# counterMeter.net
KiCad netlist of a schematic drawn in EAGLE
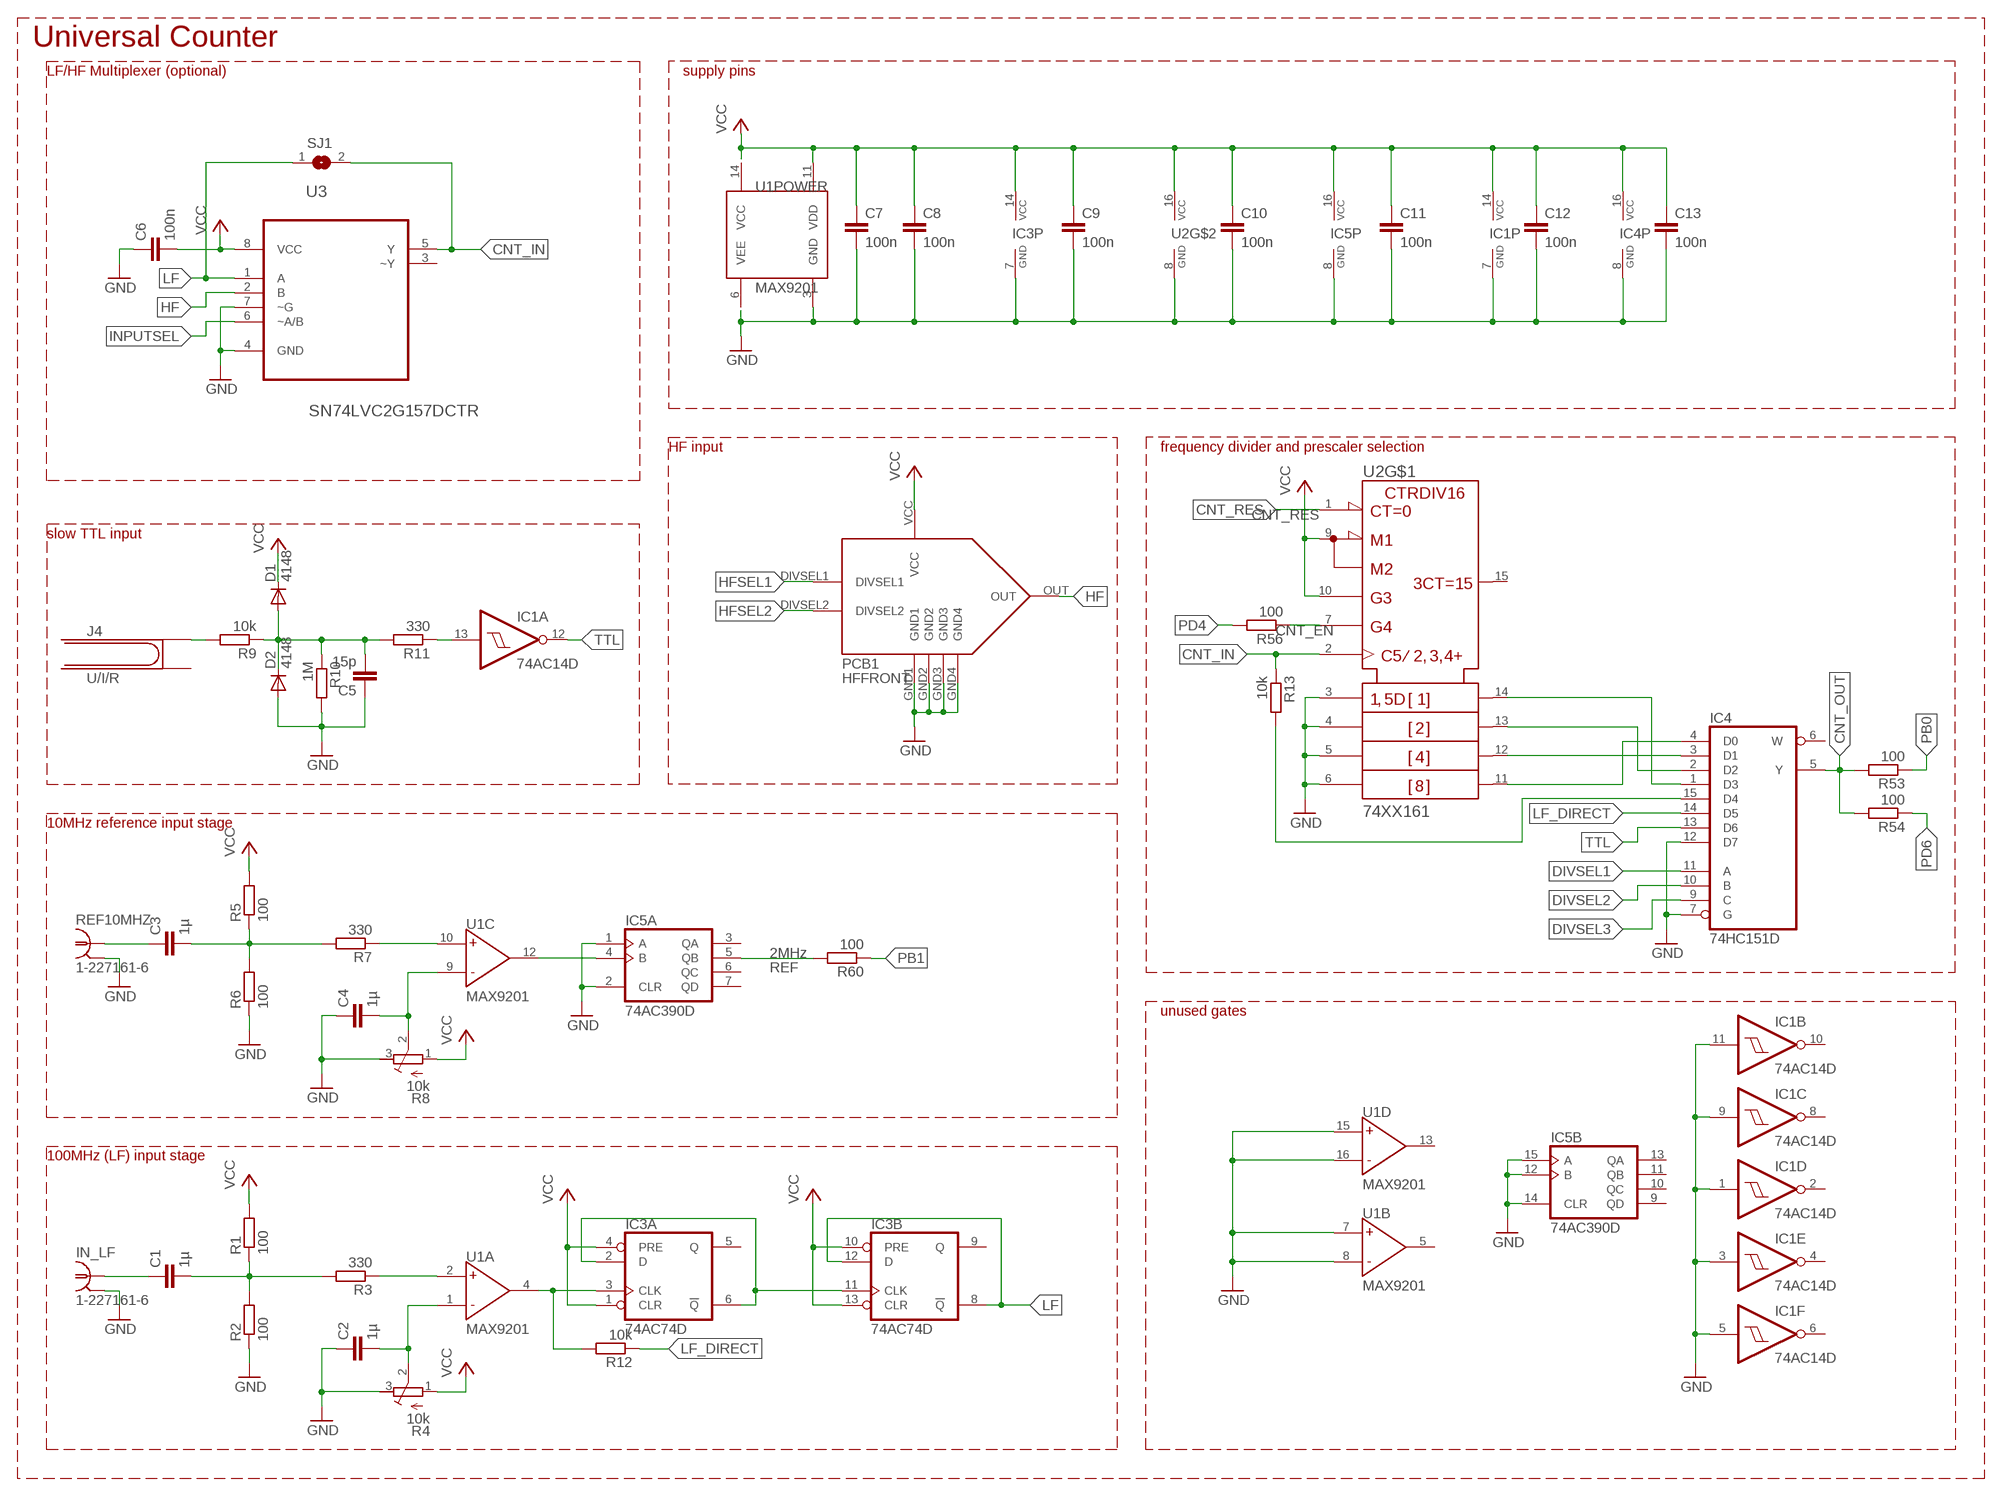
[diagram p0: schematic, sheet 1, part 1 of 2]
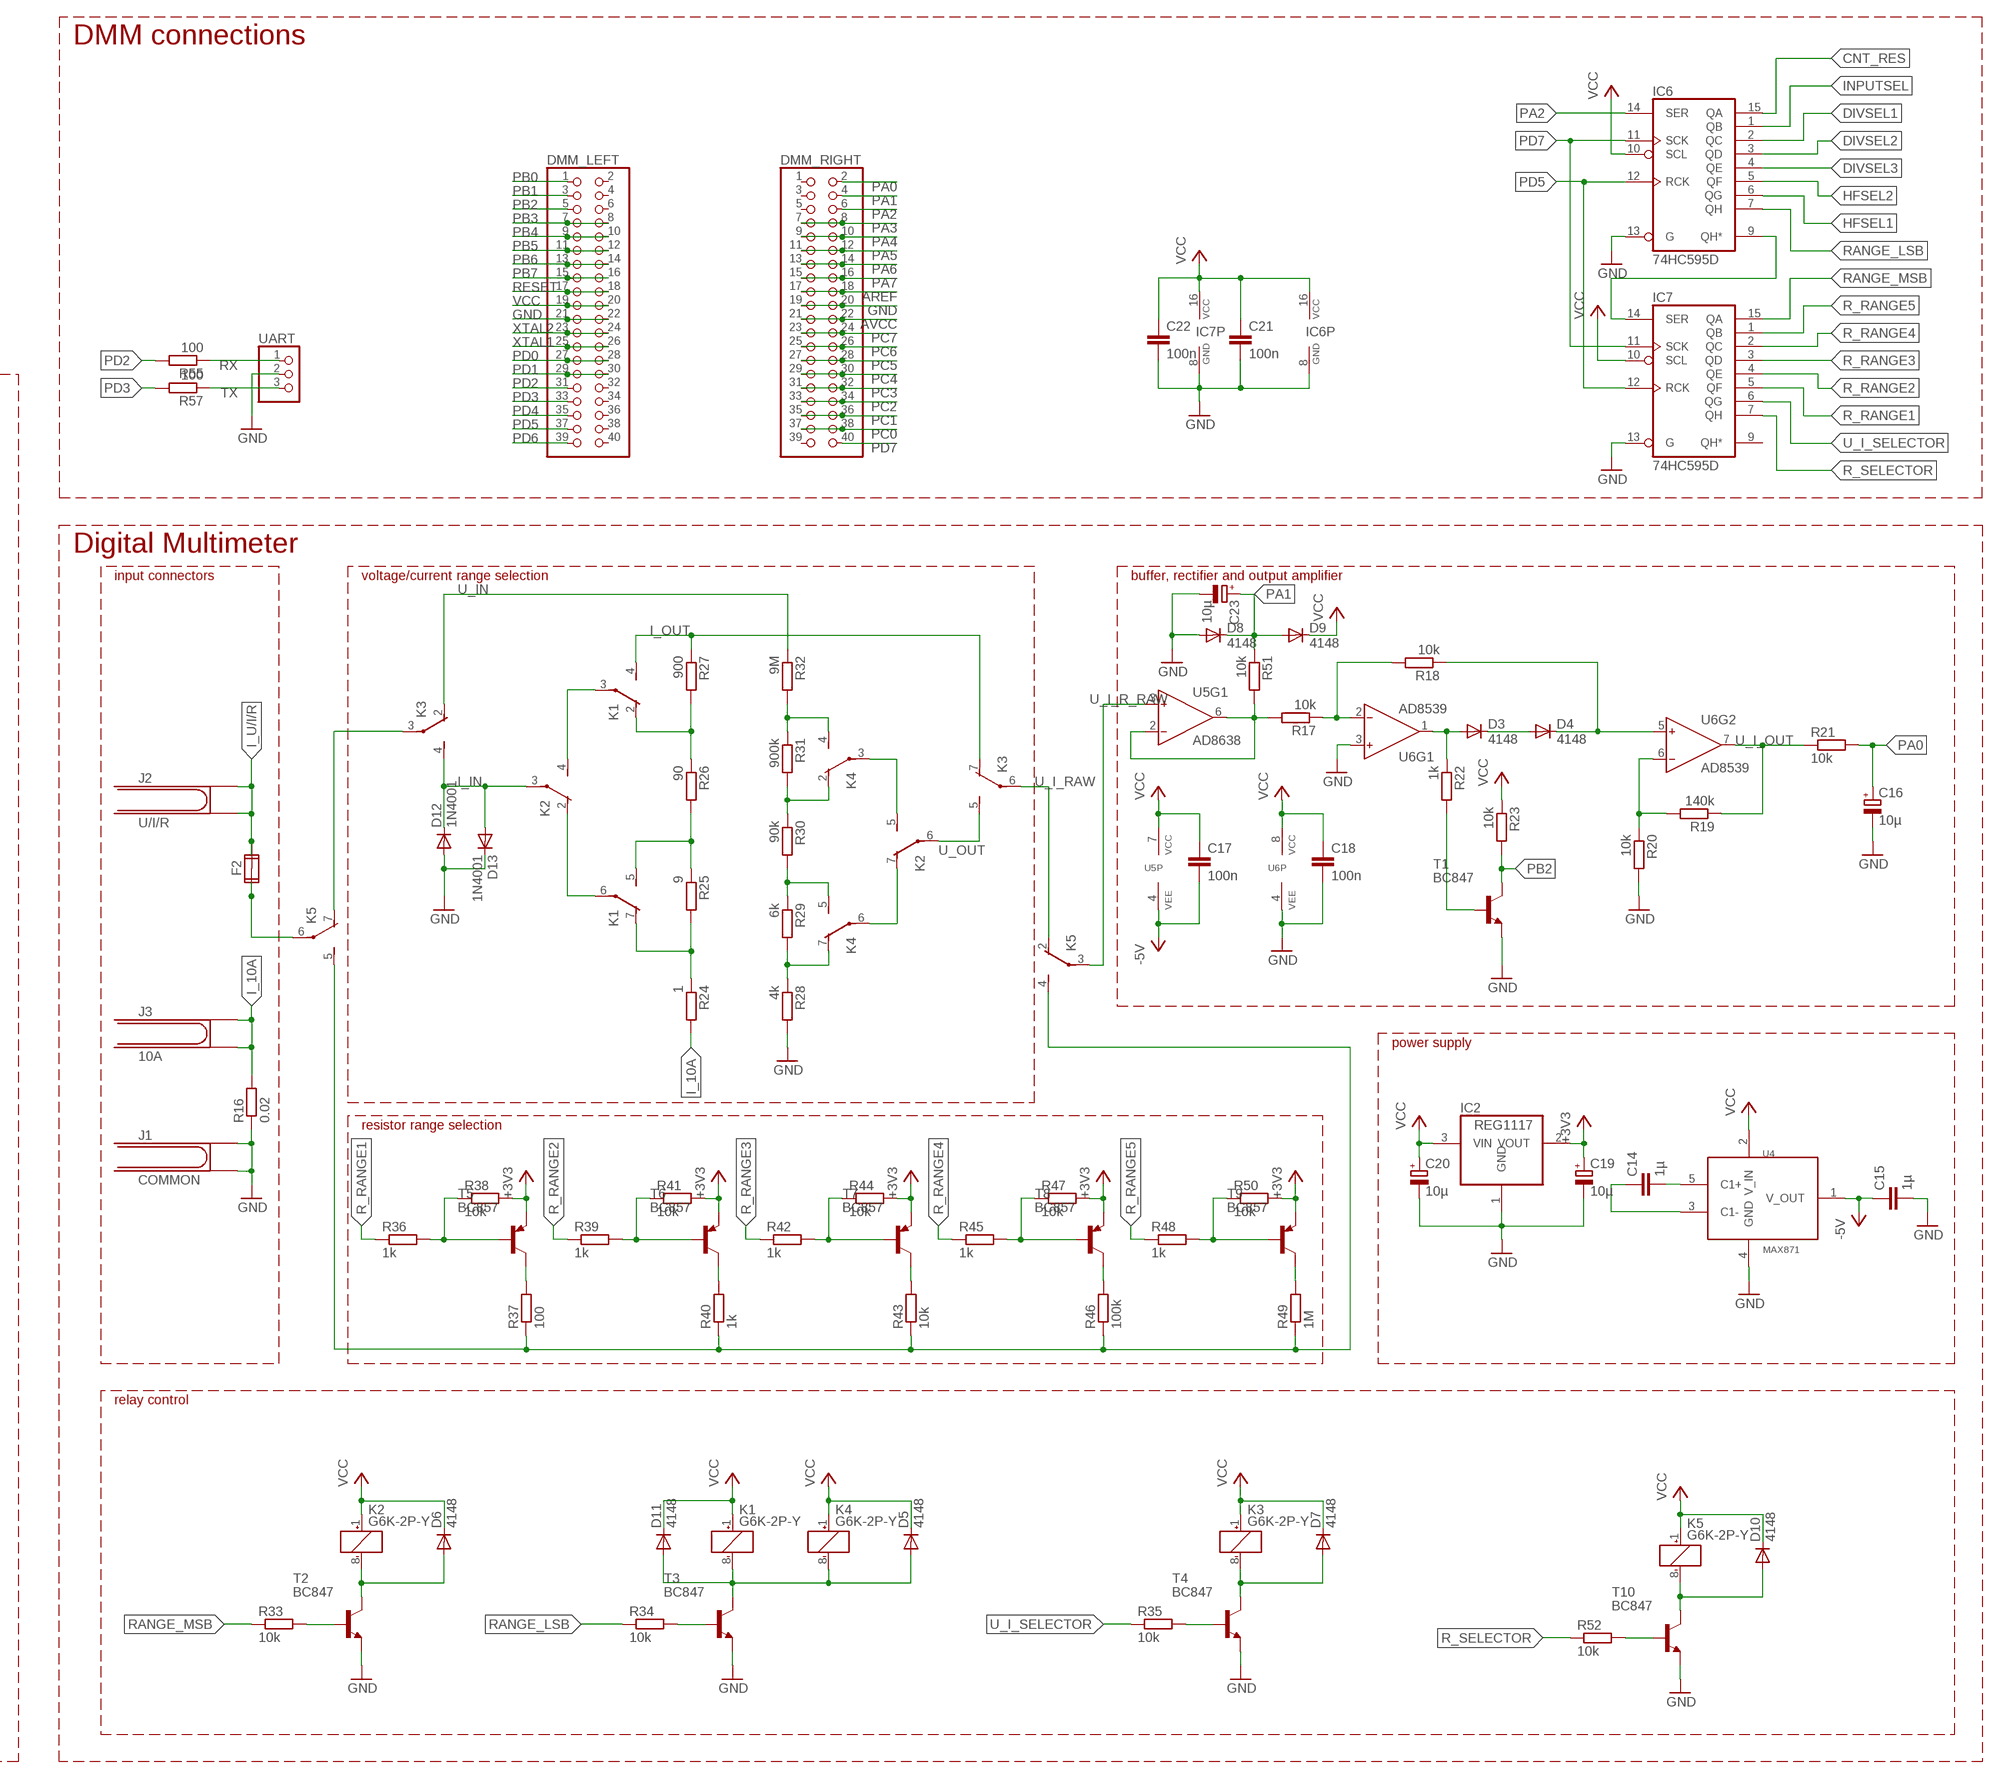
[diagram p1: schematic, sheet 1, part 2 of 2]

(export (version "E")
  (design (tool "Eeschema 10.0.6"))
  (components
    (comp (ref "C1")
      (value "1µ")
      (footprint "eagle-import:C0603")
      (libsource (lib "eagle-import") (part "C-EUC0603"))
    )
    (comp (ref "C2")
      (value "1µ")
      (footprint "eagle-import:C0603")
      (libsource (lib "eagle-import") (part "C-EUC0603"))
    )
    (comp (ref "C3")
      (value "1µ")
      (footprint "eagle-import:C0603")
      (libsource (lib "eagle-import") (part "C-EUC0603"))
    )
    (comp (ref "C4")
      (value "1µ")
      (footprint "eagle-import:C0603")
      (libsource (lib "eagle-import") (part "C-EUC0603"))
    )
    (comp (ref "C5")
      (value "15p")
      (footprint "eagle-import:C0603")
      (libsource (lib "eagle-import") (part "C-EUC0603"))
    )
    (comp (ref "C6")
      (value "100n")
      (footprint "eagle-import:C0603")
      (libsource (lib "eagle-import") (part "C-EUC0603"))
    )
    (comp (ref "C7")
      (value "100n")
      (footprint "eagle-import:C0603")
      (libsource (lib "eagle-import") (part "C-EUC0603"))
    )
    (comp (ref "C8")
      (value "100n")
      (footprint "eagle-import:C0603")
      (libsource (lib "eagle-import") (part "C-EUC0603"))
    )
    (comp (ref "C9")
      (value "100n")
      (footprint "eagle-import:C0603")
      (libsource (lib "eagle-import") (part "C-EUC0603"))
    )
    (comp (ref "C10")
      (value "100n")
      (footprint "eagle-import:C0603")
      (libsource (lib "eagle-import") (part "C-EUC0603"))
    )
    (comp (ref "C11")
      (value "100n")
      (footprint "eagle-import:C0603")
      (libsource (lib "eagle-import") (part "C-EUC0603"))
    )
    (comp (ref "C12")
      (value "100n")
      (footprint "eagle-import:C0603")
      (libsource (lib "eagle-import") (part "C-EUC0603"))
    )
    (comp (ref "C13")
      (value "100n")
      (footprint "eagle-import:C0603")
      (libsource (lib "eagle-import") (part "C-EUC0603"))
    )
    (comp (ref "C14")
      (value "1µ")
      (footprint "eagle-import:C0603")
      (libsource (lib "eagle-import") (part "C-EUC0603"))
    )
    (comp (ref "C15")
      (value "1µ")
      (footprint "eagle-import:C0603")
      (libsource (lib "eagle-import") (part "C-EUC0603"))
    )
    (comp (ref "C16")
      (value "10µ")
      (footprint "eagle-import:E2-5")
      (libsource (lib "eagle-import") (part "CPOL-EUE2-5"))
    )
    (comp (ref "C17")
      (value "100n")
      (footprint "eagle-import:C0603")
      (libsource (lib "eagle-import") (part "C-EUC0603"))
    )
    (comp (ref "C18")
      (value "100n")
      (footprint "eagle-import:C0603")
      (libsource (lib "eagle-import") (part "C-EUC0603"))
    )
    (comp (ref "C19")
      (value "10µ")
      (footprint "eagle-import:E2-5")
      (libsource (lib "eagle-import") (part "CPOL-EUE2-5"))
    )
    (comp (ref "C20")
      (value "10µ")
      (footprint "eagle-import:E2-5")
      (libsource (lib "eagle-import") (part "CPOL-EUE2-5"))
    )
    (comp (ref "C21")
      (value "100n")
      (footprint "eagle-import:C0603")
      (libsource (lib "eagle-import") (part "C-EUC0603"))
    )
    (comp (ref "C22")
      (value "100n")
      (footprint "eagle-import:C0603")
      (libsource (lib "eagle-import") (part "C-EUC0603"))
    )
    (comp (ref "C23")
      (value "10µ")
      (footprint "eagle-import:E2-5")
      (libsource (lib "eagle-import") (part "CPOL-EUE2-5"))
    )
    (comp (ref "D1")
      (value "4148")
      (footprint "eagle-import:SOD323-W")
      (libsource (lib "eagle-import") (part "DIODE-SOD323-W"))
    )
    (comp (ref "D2")
      (value "4148")
      (footprint "eagle-import:SOD323-W")
      (libsource (lib "eagle-import") (part "DIODE-SOD323-W"))
    )
    (comp (ref "D3")
      (value "4148")
      (footprint "eagle-import:SOD323-W")
      (libsource (lib "eagle-import") (part "DIODE-SOD323-W"))
    )
    (comp (ref "D4")
      (value "4148")
      (footprint "eagle-import:SOD323-W")
      (libsource (lib "eagle-import") (part "DIODE-SOD323-W"))
    )
    (comp (ref "D5")
      (value "4148")
      (footprint "eagle-import:SOD323-W")
      (libsource (lib "eagle-import") (part "DIODE-SOD323-W"))
    )
    (comp (ref "D6")
      (value "4148")
      (footprint "eagle-import:SOD323-W")
      (libsource (lib "eagle-import") (part "DIODE-SOD323-W"))
    )
    (comp (ref "D7")
      (value "4148")
      (footprint "eagle-import:SOD323-W")
      (libsource (lib "eagle-import") (part "DIODE-SOD323-W"))
    )
    (comp (ref "D8")
      (value "4148")
      (footprint "eagle-import:SOD323-W")
      (libsource (lib "eagle-import") (part "DIODE-SOD323-W"))
    )
    (comp (ref "D9")
      (value "4148")
      (footprint "eagle-import:SOD323-W")
      (libsource (lib "eagle-import") (part "DIODE-SOD323-W"))
    )
    (comp (ref "D10")
      (value "4148")
      (footprint "eagle-import:SOD323-W")
      (libsource (lib "eagle-import") (part "DIODE-SOD323-W"))
    )
    (comp (ref "D11")
      (value "4148")
      (footprint "eagle-import:SOD323-W")
      (libsource (lib "eagle-import") (part "DIODE-SOD323-W"))
    )
    (comp (ref "D12")
      (value "1N4001")
      (footprint "eagle-import:DO41-10")
      (libsource (lib "eagle-import") (part "1N4004"))
    )
    (comp (ref "D13")
      (value "1N4001")
      (footprint "eagle-import:DO41-10")
      (libsource (lib "eagle-import") (part "1N4004"))
    )
    (comp (ref "DMM_LEFT")
      (value "PINHD-2X20")
      (footprint "eagle-import:2X20")
      (libsource (lib "eagle-import") (part "PINHD-2X20"))
    )
    (comp (ref "DMM_RIGHT")
      (value "PINHD-2X20")
      (footprint "eagle-import:2X20")
      (libsource (lib "eagle-import") (part "PINHD-2X20"))
    )
    (comp (ref "F2")
      (value "FUSE2P")
      (footprint "eagle-import:FUSE1")
      (libsource (lib "eagle-import") (part "FUSE2P"))
    )
    (comp (ref "IC1")
      (value "74AC14D")
      (footprint "eagle-import:SO14")
      (libsource (lib "eagle-import") (part "7414DAC"))
    )
    (comp (ref "IC2")
      (value "REG1117")
      (footprint "eagle-import:SOT223")
      (libsource (lib "eagle-import") (part "REG1117"))
    )
    (comp (ref "IC3")
      (value "74AC74D")
      (footprint "eagle-import:SO14")
      (libsource (lib "eagle-import") (part "7474DAC"))
    )
    (comp (ref "IC4")
      (value "74HC151D")
      (footprint "eagle-import:SO16")
      (libsource (lib "eagle-import") (part "74151DHC"))
    )
    (comp (ref "IC5")
      (value "74AC390D")
      (footprint "eagle-import:SO16")
      (libsource (lib "eagle-import") (part "74390DAC"))
    )
    (comp (ref "IC6")
      (value "74HC595D")
      (footprint "eagle-import:SO16")
      (libsource (lib "eagle-import") (part "74595DHC"))
    )
    (comp (ref "IC7")
      (value "74HC595D")
      (footprint "eagle-import:SO16")
      (libsource (lib "eagle-import") (part "74595DHC"))
    )
    (comp (ref "IN_LF")
      (value "1-227161-6")
      (footprint "eagle-import:AMP_227161")
      (fields (field (name "MF") "TYCO ELECTRONICS"))
      (libsource (lib "eagle-import") (part "?2271611--6"))
    )
    (comp (ref "J1")
      (value "COMMON")
      (footprint "eagle-import:4MMJACK")
      (libsource (lib "eagle-import") (part "4MMJACK"))
    )
    (comp (ref "J2")
      (value "U/I/R")
      (footprint "eagle-import:4MMJACK")
      (libsource (lib "eagle-import") (part "4MMJACK"))
    )
    (comp (ref "J3")
      (value "10A")
      (footprint "eagle-import:4MMJACK")
      (libsource (lib "eagle-import") (part "4MMJACK"))
    )
    (comp (ref "J4")
      (value "U/I/R")
      (footprint "eagle-import:4MMJACK")
      (libsource (lib "eagle-import") (part "4MMJACK"))
    )
    (comp (ref "K1")
      (value "G6K-2P-Y")
      (footprint "eagle-import:G6K-2P-Y")
      (fields (field (name "MF") "OMRON COMPONENTS USA") (field (name "MPN") "G6K-2P-Y DC12"))
      (libsource (lib "eagle-import") (part "G6K-2P-Y"))
    )
    (comp (ref "K2")
      (value "G6K-2P-Y")
      (footprint "eagle-import:G6K-2P-Y")
      (fields (field (name "MF") "OMRON COMPONENTS USA") (field (name "MPN") "G6K-2P-Y DC12"))
      (libsource (lib "eagle-import") (part "G6K-2P-Y"))
    )
    (comp (ref "K3")
      (value "G6K-2P-Y")
      (footprint "eagle-import:G6K-2P-Y")
      (fields (field (name "MF") "OMRON COMPONENTS USA") (field (name "MPN") "G6K-2P-Y DC12"))
      (libsource (lib "eagle-import") (part "G6K-2P-Y"))
    )
    (comp (ref "K4")
      (value "G6K-2P-Y")
      (footprint "eagle-import:G6K-2P-Y")
      (fields (field (name "MF") "OMRON COMPONENTS USA") (field (name "MPN") "G6K-2P-Y DC12"))
      (libsource (lib "eagle-import") (part "G6K-2P-Y"))
    )
    (comp (ref "K5")
      (value "G6K-2P-Y")
      (footprint "eagle-import:G6K-2P-Y")
      (fields (field (name "MF") "OMRON COMPONENTS USA") (field (name "MPN") "G6K-2P-Y DC12"))
      (libsource (lib "eagle-import") (part "G6K-2P-Y"))
    )
    (comp (ref "PCB1")
      (value "HFFRONT")
      (footprint "eagle-import:HFFRONT")
      (libsource (lib "eagle-import") (part "HFFRONT"))
    )
    (comp (ref "R1")
      (value "100")
      (footprint "eagle-import:R0603")
      (libsource (lib "eagle-import") (part "R-EU_R0603"))
    )
    (comp (ref "R2")
      (value "100")
      (footprint "eagle-import:R0603")
      (libsource (lib "eagle-import") (part "R-EU_R0603"))
    )
    (comp (ref "R3")
      (value "330")
      (footprint "eagle-import:R0603")
      (libsource (lib "eagle-import") (part "R-EU_R0603"))
    )
    (comp (ref "R4")
      (value "10k")
      (footprint "eagle-import:RTRIM64W")
      (libsource (lib "eagle-import") (part "R-TRIMM64W"))
    )
    (comp (ref "R5")
      (value "100")
      (footprint "eagle-import:R0603")
      (libsource (lib "eagle-import") (part "R-EU_R0603"))
    )
    (comp (ref "R6")
      (value "100")
      (footprint "eagle-import:R0603")
      (libsource (lib "eagle-import") (part "R-EU_R0603"))
    )
    (comp (ref "R7")
      (value "330")
      (footprint "eagle-import:R0603")
      (libsource (lib "eagle-import") (part "R-EU_R0603"))
    )
    (comp (ref "R8")
      (value "10k")
      (footprint "eagle-import:RTRIM64W")
      (libsource (lib "eagle-import") (part "R-TRIMM64W"))
    )
    (comp (ref "R9")
      (value "10k")
      (footprint "eagle-import:R0603")
      (libsource (lib "eagle-import") (part "R-EU_R0603"))
    )
    (comp (ref "R10")
      (value "1M")
      (footprint "eagle-import:R0603")
      (libsource (lib "eagle-import") (part "R-EU_R0603"))
    )
    (comp (ref "R11")
      (value "330")
      (footprint "eagle-import:R0603")
      (libsource (lib "eagle-import") (part "R-EU_R0603"))
    )
    (comp (ref "R12")
      (value "10k")
      (footprint "eagle-import:R0603")
      (libsource (lib "eagle-import") (part "R-EU_R0603"))
    )
    (comp (ref "R13")
      (value "10k")
      (footprint "eagle-import:R0603")
      (libsource (lib "eagle-import") (part "R-EU_R0603"))
    )
    (comp (ref "R16")
      (value "0.02")
      (footprint "eagle-import:R2512")
      (libsource (lib "eagle-import") (part "R-EU_R2512"))
    )
    (comp (ref "R17")
      (value "10k")
      (footprint "eagle-import:R0603")
      (libsource (lib "eagle-import") (part "R-EU_R0603"))
    )
    (comp (ref "R18")
      (value "10k")
      (footprint "eagle-import:R0603")
      (libsource (lib "eagle-import") (part "R-EU_R0603"))
    )
    (comp (ref "R19")
      (value "140k")
      (footprint "eagle-import:R0603")
      (libsource (lib "eagle-import") (part "R-EU_R0603"))
    )
    (comp (ref "R20")
      (value "10k")
      (footprint "eagle-import:R0603")
      (libsource (lib "eagle-import") (part "R-EU_R0603"))
    )
    (comp (ref "R21")
      (value "10k")
      (footprint "eagle-import:R0603")
      (libsource (lib "eagle-import") (part "R-EU_R0603"))
    )
    (comp (ref "R22")
      (value "1k")
      (footprint "eagle-import:R0603")
      (libsource (lib "eagle-import") (part "R-EU_R0603"))
    )
    (comp (ref "R23")
      (value "10k")
      (footprint "eagle-import:R0603")
      (libsource (lib "eagle-import") (part "R-EU_R0603"))
    )
    (comp (ref "R24")
      (value "1")
      (footprint "eagle-import:R0603")
      (libsource (lib "eagle-import") (part "R-EU_R0603"))
    )
    (comp (ref "R25")
      (value "9")
      (footprint "eagle-import:R0603")
      (libsource (lib "eagle-import") (part "R-EU_R0603"))
    )
    (comp (ref "R26")
      (value "90")
      (footprint "eagle-import:R0603")
      (libsource (lib "eagle-import") (part "R-EU_R0603"))
    )
    (comp (ref "R27")
      (value "900")
      (footprint "eagle-import:R0603")
      (libsource (lib "eagle-import") (part "R-EU_R0603"))
    )
    (comp (ref "R28")
      (value "4k")
      (footprint "eagle-import:R0603")
      (libsource (lib "eagle-import") (part "R-EU_R0603"))
    )
    (comp (ref "R29")
      (value "6k")
      (footprint "eagle-import:R0603")
      (libsource (lib "eagle-import") (part "R-EU_R0603"))
    )
    (comp (ref "R30")
      (value "90k")
      (footprint "eagle-import:R0603")
      (libsource (lib "eagle-import") (part "R-EU_R0603"))
    )
    (comp (ref "R31")
      (value "900k")
      (footprint "eagle-import:R0603")
      (libsource (lib "eagle-import") (part "R-EU_R0603"))
    )
    (comp (ref "R32")
      (value "9M")
      (footprint "eagle-import:R0603")
      (libsource (lib "eagle-import") (part "R-EU_R0603"))
    )
    (comp (ref "R33")
      (value "10k")
      (footprint "eagle-import:R0603")
      (libsource (lib "eagle-import") (part "R-EU_R0603"))
    )
    (comp (ref "R34")
      (value "10k")
      (footprint "eagle-import:R0603")
      (libsource (lib "eagle-import") (part "R-EU_R0603"))
    )
    (comp (ref "R35")
      (value "10k")
      (footprint "eagle-import:R0603")
      (libsource (lib "eagle-import") (part "R-EU_R0603"))
    )
    (comp (ref "R36")
      (value "1k")
      (footprint "eagle-import:R0603")
      (libsource (lib "eagle-import") (part "R-EU_R0603"))
    )
    (comp (ref "R37")
      (value "100")
      (footprint "eagle-import:R0603")
      (libsource (lib "eagle-import") (part "R-EU_R0603"))
    )
    (comp (ref "R38")
      (value "10k")
      (footprint "eagle-import:R0603")
      (libsource (lib "eagle-import") (part "R-EU_R0603"))
    )
    (comp (ref "R39")
      (value "1k")
      (footprint "eagle-import:R0603")
      (libsource (lib "eagle-import") (part "R-EU_R0603"))
    )
    (comp (ref "R40")
      (value "1k")
      (footprint "eagle-import:R0603")
      (libsource (lib "eagle-import") (part "R-EU_R0603"))
    )
    (comp (ref "R41")
      (value "10k")
      (footprint "eagle-import:R0603")
      (libsource (lib "eagle-import") (part "R-EU_R0603"))
    )
    (comp (ref "R42")
      (value "1k")
      (footprint "eagle-import:R0603")
      (libsource (lib "eagle-import") (part "R-EU_R0603"))
    )
    (comp (ref "R43")
      (value "10k")
      (footprint "eagle-import:R0603")
      (libsource (lib "eagle-import") (part "R-EU_R0603"))
    )
    (comp (ref "R44")
      (value "10k")
      (footprint "eagle-import:R0603")
      (libsource (lib "eagle-import") (part "R-EU_R0603"))
    )
    (comp (ref "R45")
      (value "1k")
      (footprint "eagle-import:R0603")
      (libsource (lib "eagle-import") (part "R-EU_R0603"))
    )
    (comp (ref "R46")
      (value "100k")
      (footprint "eagle-import:R0603")
      (libsource (lib "eagle-import") (part "R-EU_R0603"))
    )
    (comp (ref "R47")
      (value "10k")
      (footprint "eagle-import:R0603")
      (libsource (lib "eagle-import") (part "R-EU_R0603"))
    )
    (comp (ref "R48")
      (value "1k")
      (footprint "eagle-import:R0603")
      (libsource (lib "eagle-import") (part "R-EU_R0603"))
    )
    (comp (ref "R49")
      (value "1M")
      (footprint "eagle-import:R0603")
      (libsource (lib "eagle-import") (part "R-EU_R0603"))
    )
    (comp (ref "R50")
      (value "10k")
      (footprint "eagle-import:R0603")
      (libsource (lib "eagle-import") (part "R-EU_R0603"))
    )
    (comp (ref "R51")
      (value "10k")
      (footprint "eagle-import:R0603")
      (libsource (lib "eagle-import") (part "R-EU_R0603"))
    )
    (comp (ref "R52")
      (value "10k")
      (footprint "eagle-import:R0603")
      (libsource (lib "eagle-import") (part "R-EU_R0603"))
    )
    (comp (ref "R53")
      (value "100")
      (footprint "eagle-import:R0603")
      (libsource (lib "eagle-import") (part "R-EU_R0603"))
    )
    (comp (ref "R54")
      (value "100")
      (footprint "eagle-import:R0603")
      (libsource (lib "eagle-import") (part "R-EU_R0603"))
    )
    (comp (ref "R55")
      (value "100")
      (footprint "eagle-import:R0603")
      (libsource (lib "eagle-import") (part "R-EU_R0603"))
    )
    (comp (ref "R56")
      (value "100")
      (footprint "eagle-import:R0603")
      (libsource (lib "eagle-import") (part "R-EU_R0603"))
    )
    (comp (ref "R57")
      (value "100")
      (footprint "eagle-import:R0603")
      (libsource (lib "eagle-import") (part "R-EU_R0603"))
    )
    (comp (ref "R60")
      (value "100")
      (footprint "eagle-import:R0603")
      (libsource (lib "eagle-import") (part "R-EU_R0603"))
    )
    (comp (ref "REF10MHZ")
      (value "1-227161-6")
      (footprint "eagle-import:AMP_227161")
      (fields (field (name "MF") "TYCO ELECTRONICS"))
      (libsource (lib "eagle-import") (part "?2271611--6"))
    )
    (comp (ref "SJ1") (value "SJ") (footprint "eagle-import:SJ") (libsource (lib "eagle-import") (part "SJ")))
    (comp (ref "T1")
      (value "BC847")
      (footprint "eagle-import:SOT23")
      (libsource (lib "eagle-import") (part "BC847"))
    )
    (comp (ref "T2")
      (value "BC847")
      (footprint "eagle-import:SOT23")
      (libsource (lib "eagle-import") (part "BC847"))
    )
    (comp (ref "T3")
      (value "BC847")
      (footprint "eagle-import:SOT23")
      (libsource (lib "eagle-import") (part "BC847"))
    )
    (comp (ref "T4")
      (value "BC847")
      (footprint "eagle-import:SOT23")
      (libsource (lib "eagle-import") (part "BC847"))
    )
    (comp (ref "T5")
      (value "BC857")
      (footprint "eagle-import:SOT23-BEC")
      (libsource (lib "eagle-import") (part "-PNP-SOT23-BECBC857C"))
    )
    (comp (ref "T6")
      (value "BC857")
      (footprint "eagle-import:SOT23-BEC")
      (libsource (lib "eagle-import") (part "-PNP-SOT23-BECBC857C"))
    )
    (comp (ref "T7")
      (value "BC857")
      (footprint "eagle-import:SOT23-BEC")
      (libsource (lib "eagle-import") (part "-PNP-SOT23-BECBC857C"))
    )
    (comp (ref "T8")
      (value "BC857")
      (footprint "eagle-import:SOT23-BEC")
      (libsource (lib "eagle-import") (part "-PNP-SOT23-BECBC857C"))
    )
    (comp (ref "T9")
      (value "BC857")
      (footprint "eagle-import:SOT23-BEC")
      (libsource (lib "eagle-import") (part "-PNP-SOT23-BECBC857C"))
    )
    (comp (ref "T10")
      (value "BC847")
      (footprint "eagle-import:SOT23")
      (libsource (lib "eagle-import") (part "BC847"))
    )
    (comp (ref "U1")
      (value "MAX9201")
      (footprint "eagle-import:SOIC16")
      (libsource (lib "eagle-import") (part "MAX9201"))
    )
    (comp (ref "U2")
      (value "74XX161")
      (footprint "eagle-import:SOIC16")
      (libsource (lib "eagle-import") (part "74XX161"))
    )
    (comp (ref "U3")
      (value "SN74LVC2G157DCTR")
      (footprint "eagle-import:SOP65P400X130-8N")
      (libsource (lib "eagle-import") (part "SN74LVC2G157DCTR"))
    )
    (comp (ref "U4")
      (value "MAX871")
      (footprint "eagle-import:SOT23-5")
      (libsource (lib "eagle-import") (part "MAX871"))
    )
    (comp (ref "U5")
      (value "AD8638")
      (footprint "eagle-import:SOIC8")
      (libsource (lib "eagle-import") (part "AD8638"))
    )
    (comp (ref "U6")
      (value "AD8539")
      (footprint "eagle-import:SOIC8")
      (libsource (lib "eagle-import") (part "AD8539"))
    )
    (comp (ref "UART")
      (value "PINHD-1X3")
      (footprint "eagle-import:1X03")
      (libsource (lib "eagle-import") (part "PINHD-1X3"))
    )
  )
  (nets
    (net (code "1") (name "+3V3") (class "Default")
      (node (ref "C19") (pin "+") (pinfunction "+_+") (pintype "passive"))
      (node (ref "IC2") (pin "2") (pinfunction "VOUT_2") (pintype "output"))
      (node (ref "R38") (pin "2") (pinfunction "2_2") (pintype "passive"))
      (node (ref "R41") (pin "2") (pinfunction "2_2") (pintype "passive"))
      (node (ref "R44") (pin "2") (pinfunction "2_2") (pintype "passive"))
      (node (ref "R47") (pin "2") (pinfunction "2_2") (pintype "passive"))
      (node (ref "R50") (pin "2") (pinfunction "2_2") (pintype "passive"))
      (node (ref "T5") (pin "E") (pinfunction "E_E") (pintype "passive"))
      (node (ref "T6") (pin "E") (pinfunction "E_E") (pintype "passive"))
      (node (ref "T7") (pin "E") (pinfunction "E_E") (pintype "passive"))
      (node (ref "T8") (pin "E") (pinfunction "E_E") (pintype "passive"))
      (node (ref "T9") (pin "E") (pinfunction "E_E") (pintype "passive"))
    )
    (net (code "2") (name "-5V") (class "Default")
      (node (ref "C15") (pin "1") (pinfunction "1_1") (pintype "passive"))
      (node (ref "C17") (pin "2") (pinfunction "2_2") (pintype "passive"))
      (node (ref "U4") (pin "1") (pinfunction "V_OUT_1") (pintype "bidirectional"))
      (node (ref "U5") (pin "4") (pinfunction "VEE_4") (pintype "bidirectional"))
    )
    (net (code "3") (name "/AREF") (class "Default")
      (node (ref "DMM_RIGHT") (pin "17") (pinfunction "17_17") (pintype "passive"))
      (node (ref "DMM_RIGHT") (pin "18") (pinfunction "18_18") (pintype "passive"))
    )
    (net (code "4") (name "/AVCC") (class "Default")
      (node (ref "DMM_RIGHT") (pin "21") (pinfunction "21_21") (pintype "passive"))
      (node (ref "DMM_RIGHT") (pin "22") (pinfunction "22_22") (pintype "passive"))
    )
    (net (code "5") (name "/CNT_EN") (class "Default")
      (node (ref "R56") (pin "1") (pinfunction "1_1") (pintype "passive"))
      (node (ref "U2") (pin "7") (pinfunction "ENP_7") (pintype "input"))
    )
    (net (code "6") (name "/I_IN") (class "Default")
      (node (ref "D12") (pin "C") (pinfunction "C_C") (pintype "passive"))
      (node (ref "D13") (pin "A") (pinfunction "A_A") (pintype "passive"))
      (node (ref "K2") (pin "3") (pinfunction "P_3") (pintype "passive"))
      (node (ref "K3") (pin "4") (pinfunction "S_4") (pintype "passive"))
    )
    (net (code "7") (name "/I_OUT") (class "Default")
      (node (ref "K1") (pin "4") (pinfunction "S_4") (pintype "passive"))
      (node (ref "K3") (pin "7") (pinfunction "O_7") (pintype "passive"))
      (node (ref "R27") (pin "1") (pinfunction "1_1") (pintype "passive"))
    )
    (net (code "8") (name "/PA3") (class "Default")
      (node (ref "DMM_RIGHT") (pin "7") (pinfunction "7_7") (pintype "passive"))
      (node (ref "DMM_RIGHT") (pin "8") (pinfunction "8_8") (pintype "passive"))
    )
    (net (code "9") (name "/PA4") (class "Default")
      (node (ref "DMM_RIGHT") (pin "10") (pinfunction "10_10") (pintype "passive"))
      (node (ref "DMM_RIGHT") (pin "9") (pinfunction "9_9") (pintype "passive"))
    )
    (net (code "10") (name "/PA5") (class "Default")
      (node (ref "DMM_RIGHT") (pin "11") (pinfunction "11_11") (pintype "passive"))
      (node (ref "DMM_RIGHT") (pin "12") (pinfunction "12_12") (pintype "passive"))
    )
    (net (code "11") (name "/PA6") (class "Default")
      (node (ref "DMM_RIGHT") (pin "13") (pinfunction "13_13") (pintype "passive"))
      (node (ref "DMM_RIGHT") (pin "14") (pinfunction "14_14") (pintype "passive"))
    )
    (net (code "12") (name "/PA7") (class "Default")
      (node (ref "DMM_RIGHT") (pin "15") (pinfunction "15_15") (pintype "passive"))
      (node (ref "DMM_RIGHT") (pin "16") (pinfunction "16_16") (pintype "passive"))
    )
    (net (code "13") (name "/PB3") (class "Default")
      (node (ref "DMM_LEFT") (pin "7") (pinfunction "7_7") (pintype "passive"))
      (node (ref "DMM_LEFT") (pin "8") (pinfunction "8_8") (pintype "passive"))
    )
    (net (code "14") (name "/PB4") (class "Default")
      (node (ref "DMM_LEFT") (pin "10") (pinfunction "10_10") (pintype "passive"))
      (node (ref "DMM_LEFT") (pin "9") (pinfunction "9_9") (pintype "passive"))
    )
    (net (code "15") (name "/PB5") (class "Default")
      (node (ref "DMM_LEFT") (pin "11") (pinfunction "11_11") (pintype "passive"))
      (node (ref "DMM_LEFT") (pin "12") (pinfunction "12_12") (pintype "passive"))
    )
    (net (code "16") (name "/PB6") (class "Default")
      (node (ref "DMM_LEFT") (pin "13") (pinfunction "13_13") (pintype "passive"))
      (node (ref "DMM_LEFT") (pin "14") (pinfunction "14_14") (pintype "passive"))
    )
    (net (code "17") (name "/PB7") (class "Default")
      (node (ref "DMM_LEFT") (pin "15") (pinfunction "15_15") (pintype "passive"))
      (node (ref "DMM_LEFT") (pin "16") (pinfunction "16_16") (pintype "passive"))
    )
    (net (code "18") (name "/PC0") (class "Default")
      (node (ref "DMM_RIGHT") (pin "37") (pinfunction "37_37") (pintype "passive"))
      (node (ref "DMM_RIGHT") (pin "38") (pinfunction "38_38") (pintype "passive"))
    )
    (net (code "19") (name "/PC1") (class "Default")
      (node (ref "DMM_RIGHT") (pin "35") (pinfunction "35_35") (pintype "passive"))
      (node (ref "DMM_RIGHT") (pin "36") (pinfunction "36_36") (pintype "passive"))
    )
    (net (code "20") (name "/PC2") (class "Default")
      (node (ref "DMM_RIGHT") (pin "33") (pinfunction "33_33") (pintype "passive"))
      (node (ref "DMM_RIGHT") (pin "34") (pinfunction "34_34") (pintype "passive"))
    )
    (net (code "21") (name "/PC3") (class "Default")
      (node (ref "DMM_RIGHT") (pin "31") (pinfunction "31_31") (pintype "passive"))
      (node (ref "DMM_RIGHT") (pin "32") (pinfunction "32_32") (pintype "passive"))
    )
    (net (code "22") (name "/PC4") (class "Default")
      (node (ref "DMM_RIGHT") (pin "29") (pinfunction "29_29") (pintype "passive"))
      (node (ref "DMM_RIGHT") (pin "30") (pinfunction "30_30") (pintype "passive"))
    )
    (net (code "23") (name "/PC5") (class "Default")
      (node (ref "DMM_RIGHT") (pin "27") (pinfunction "27_27") (pintype "passive"))
      (node (ref "DMM_RIGHT") (pin "28") (pinfunction "28_28") (pintype "passive"))
    )
    (net (code "24") (name "/PC6") (class "Default")
      (node (ref "DMM_RIGHT") (pin "25") (pinfunction "25_25") (pintype "passive"))
      (node (ref "DMM_RIGHT") (pin "26") (pinfunction "26_26") (pintype "passive"))
    )
    (net (code "25") (name "/PC7") (class "Default")
      (node (ref "DMM_RIGHT") (pin "23") (pinfunction "23_23") (pintype "passive"))
      (node (ref "DMM_RIGHT") (pin "24") (pinfunction "24_24") (pintype "passive"))
    )
    (net (code "26") (name "/PD0") (class "Default")
      (node (ref "DMM_LEFT") (pin "27") (pinfunction "27_27") (pintype "passive"))
      (node (ref "DMM_LEFT") (pin "28") (pinfunction "28_28") (pintype "passive"))
    )
    (net (code "27") (name "/PD1") (class "Default")
      (node (ref "DMM_LEFT") (pin "29") (pinfunction "29_29") (pintype "passive"))
      (node (ref "DMM_LEFT") (pin "30") (pinfunction "30_30") (pintype "passive"))
    )
    (net (code "28") (name "/REF") (class "Default")
      (node (ref "IC5") (pin "5") (pinfunction "QB_5") (pintype "output"))
      (node (ref "R60") (pin "2") (pinfunction "2_2") (pintype "passive"))
    )
    (net (code "29") (name "/RESET") (class "Default")
      (node (ref "DMM_LEFT") (pin "17") (pinfunction "17_17") (pintype "passive"))
      (node (ref "DMM_LEFT") (pin "18") (pinfunction "18_18") (pintype "passive"))
    )
    (net (code "30") (name "/RX") (class "Default")
      (node (ref "R55") (pin "1") (pinfunction "1_1") (pintype "passive"))
      (node (ref "UART") (pin "1") (pinfunction "1_1") (pintype "passive"))
    )
    (net (code "31") (name "/TX") (class "Default")
      (node (ref "R57") (pin "1") (pinfunction "1_1") (pintype "passive"))
      (node (ref "UART") (pin "3") (pinfunction "3_3") (pintype "passive"))
    )
    (net (code "32") (name "/U_IN") (class "Default")
      (node (ref "K3") (pin "2") (pinfunction "O_2") (pintype "passive"))
      (node (ref "R32") (pin "1") (pinfunction "1_1") (pintype "passive"))
    )
    (net (code "33") (name "/U_I_OUT") (class "Default")
      (node (ref "R19") (pin "1") (pinfunction "1_1") (pintype "passive"))
      (node (ref "R21") (pin "1") (pinfunction "1_1") (pintype "passive"))
      (node (ref "U6") (pin "7") (pinfunction "OUT_7") (pintype "output"))
    )
    (net (code "34") (name "/U_I_RAW") (class "Default")
      (node (ref "K3") (pin "6") (pinfunction "P_6") (pintype "passive"))
      (node (ref "K5") (pin "2") (pinfunction "O_2") (pintype "passive"))
    )
    (net (code "35") (name "/U_I_R_RAW") (class "Default")
      (node (ref "K5") (pin "3") (pinfunction "P_3") (pintype "passive"))
      (node (ref "U5") (pin "3") (pinfunction "IN+_3") (pintype "input"))
    )
    (net (code "36") (name "/U_OUT") (class "Default")
      (node (ref "K2") (pin "6") (pinfunction "P_6") (pintype "passive"))
      (node (ref "K3") (pin "5") (pinfunction "S_5") (pintype "passive"))
    )
    (net (code "37") (name "/XTAL1") (class "Default")
      (node (ref "DMM_LEFT") (pin "25") (pinfunction "25_25") (pintype "passive"))
      (node (ref "DMM_LEFT") (pin "26") (pinfunction "26_26") (pintype "passive"))
    )
    (net (code "38") (name "/XTAL2") (class "Default")
      (node (ref "DMM_LEFT") (pin "23") (pinfunction "23_23") (pintype "passive"))
      (node (ref "DMM_LEFT") (pin "24") (pinfunction "24_24") (pintype "passive"))
    )
    (net (code "39") (name "CNT_IN") (class "Default")
      (node (ref "R13") (pin "1") (pinfunction "1_1") (pintype "passive"))
      (node (ref "SJ1") (pin "2") (pinfunction "2_2") (pintype "passive"))
      (node (ref "U2") (pin "2") (pinfunction "CLK_2") (pintype "input"))
      (node (ref "U3") (pin "5") (pinfunction "Y_5") (pintype "output"))
    )
    (net (code "40") (name "CNT_OUT") (class "Default")
      (node (ref "IC4") (pin "5") (pinfunction "Y_5") (pintype "output"))
      (node (ref "R53") (pin "2") (pinfunction "2_2") (pintype "passive"))
      (node (ref "R54") (pin "2") (pinfunction "2_2") (pintype "passive"))
    )
    (net (code "41") (name "CNT_RES") (class "Default")
      (node (ref "IC6") (pin "15") (pinfunction "QA_15") (pintype "tri_state"))
      (node (ref "U2") (pin "1") (pinfunction "~{CLR}_1") (pintype "input"))
    )
    (net (code "42") (name "DIVSEL1") (class "Default")
      (node (ref "IC4") (pin "11") (pinfunction "A_11") (pintype "input"))
      (node (ref "IC6") (pin "2") (pinfunction "QC_2") (pintype "tri_state"))
    )
    (net (code "43") (name "DIVSEL2") (class "Default")
      (node (ref "IC4") (pin "10") (pinfunction "B_10") (pintype "input"))
      (node (ref "IC6") (pin "3") (pinfunction "QD_3") (pintype "tri_state"))
    )
    (net (code "44") (name "DIVSEL3") (class "Default")
      (node (ref "IC4") (pin "9") (pinfunction "C_9") (pintype "input"))
      (node (ref "IC6") (pin "4") (pinfunction "QE_4") (pintype "tri_state"))
    )
    (net (code "45") (name "GND") (class "Default")
      (node (ref "C10") (pin "2") (pinfunction "2_2") (pintype "passive"))
      (node (ref "C11") (pin "2") (pinfunction "2_2") (pintype "passive"))
      (node (ref "C12") (pin "2") (pinfunction "2_2") (pintype "passive"))
      (node (ref "C13") (pin "2") (pinfunction "2_2") (pintype "passive"))
      (node (ref "C15") (pin "2") (pinfunction "2_2") (pintype "passive"))
      (node (ref "C16") (pin "-") (pinfunction "-_-") (pintype "passive"))
      (node (ref "C18") (pin "2") (pinfunction "2_2") (pintype "passive"))
      (node (ref "C19") (pin "-") (pinfunction "-_-") (pintype "passive"))
      (node (ref "C2") (pin "1") (pinfunction "1_1") (pintype "passive"))
      (node (ref "C20") (pin "-") (pinfunction "-_-") (pintype "passive"))
      (node (ref "C21") (pin "2") (pinfunction "2_2") (pintype "passive"))
      (node (ref "C22") (pin "2") (pinfunction "2_2") (pintype "passive"))
      (node (ref "C23") (pin "-") (pinfunction "-_-") (pintype "passive"))
      (node (ref "C4") (pin "1") (pinfunction "1_1") (pintype "passive"))
      (node (ref "C5") (pin "1") (pinfunction "1_1") (pintype "passive"))
      (node (ref "C6") (pin "1") (pinfunction "1_1") (pintype "passive"))
      (node (ref "C7") (pin "2") (pinfunction "2_2") (pintype "passive"))
      (node (ref "C8") (pin "2") (pinfunction "2_2") (pintype "passive"))
      (node (ref "C9") (pin "2") (pinfunction "2_2") (pintype "passive"))
      (node (ref "D12") (pin "A") (pinfunction "A_A") (pintype "passive"))
      (node (ref "D13") (pin "C") (pinfunction "C_C") (pintype "passive"))
      (node (ref "D2") (pin "A") (pinfunction "A_A") (pintype "passive"))
      (node (ref "D8") (pin "A") (pinfunction "A_A") (pintype "passive"))
      (node (ref "DMM_LEFT") (pin "21") (pinfunction "21_21") (pintype "passive"))
      (node (ref "DMM_LEFT") (pin "22") (pinfunction "22_22") (pintype "passive"))
      (node (ref "DMM_RIGHT") (pin "19") (pinfunction "19_19") (pintype "passive"))
      (node (ref "DMM_RIGHT") (pin "20") (pinfunction "20_20") (pintype "passive"))
      (node (ref "IC1") (pin "1") (pinfunction "I_1") (pintype "input"))
      (node (ref "IC1") (pin "11") (pinfunction "I_11") (pintype "input"))
      (node (ref "IC1") (pin "3") (pinfunction "I_3") (pintype "input"))
      (node (ref "IC1") (pin "5") (pinfunction "I_5") (pintype "input"))
      (node (ref "IC1") (pin "7") (pinfunction "GND_7") (pintype "power_in"))
      (node (ref "IC1") (pin "9") (pinfunction "I_9") (pintype "input"))
      (node (ref "IC2") (pin "1") (pinfunction "GND_1") (pintype "power_in"))
      (node (ref "IC3") (pin "7") (pinfunction "GND_7") (pintype "power_in"))
      (node (ref "IC4") (pin "12") (pinfunction "D7_12") (pintype "input"))
      (node (ref "IC4") (pin "7") (pinfunction "G_7") (pintype "input"))
      (node (ref "IC4") (pin "8") (pinfunction "GND_8") (pintype "power_in"))
      (node (ref "IC5") (pin "1") (pinfunction "A_1") (pintype "input"))
      (node (ref "IC5") (pin "12") (pinfunction "B_12") (pintype "input"))
      (node (ref "IC5") (pin "14") (pinfunction "CLR_14") (pintype "input"))
      (node (ref "IC5") (pin "15") (pinfunction "A_15") (pintype "input"))
      (node (ref "IC5") (pin "2") (pinfunction "CLR_2") (pintype "input"))
      (node (ref "IC5") (pin "8") (pinfunction "GND_8") (pintype "power_in"))
      (node (ref "IC6") (pin "13") (pinfunction "G_13") (pintype "input"))
      (node (ref "IC6") (pin "8") (pinfunction "GND_8") (pintype "power_in"))
      (node (ref "IC7") (pin "13") (pinfunction "G_13") (pintype "input"))
      (node (ref "IC7") (pin "8") (pinfunction "GND_8") (pintype "power_in"))
      (node (ref "IN_LF") (pin "2") (pinfunction "2_2") (pintype "passive"))
      (node (ref "J1") (pin "1@1") (pinfunction "1_1@1") (pintype "bidirectional"))
      (node (ref "J1") (pin "1@2") (pinfunction "2_1@2") (pintype "bidirectional"))
      (node (ref "PCB1") (pin "GND1") (pinfunction "GND1_GND1") (pintype "bidirectional"))
      (node (ref "PCB1") (pin "GND2") (pinfunction "GND2_GND2") (pintype "bidirectional"))
      (node (ref "PCB1") (pin "GND3") (pinfunction "GND3_GND3") (pintype "bidirectional"))
      (node (ref "PCB1") (pin "GND4") (pinfunction "GND4_GND4") (pintype "bidirectional"))
      (node (ref "R10") (pin "2") (pinfunction "2_2") (pintype "passive"))
      (node (ref "R16") (pin "1") (pinfunction "1_1") (pintype "passive"))
      (node (ref "R2") (pin "1") (pinfunction "1_1") (pintype "passive"))
      (node (ref "R20") (pin "2") (pinfunction "2_2") (pintype "passive"))
      (node (ref "R28") (pin "2") (pinfunction "2_2") (pintype "passive"))
      (node (ref "R4") (pin "3") (pinfunction "A_3") (pintype "passive"))
      (node (ref "R6") (pin "1") (pinfunction "1_1") (pintype "passive"))
      (node (ref "R8") (pin "3") (pinfunction "A_3") (pintype "passive"))
      (node (ref "REF10MHZ") (pin "2") (pinfunction "2_2") (pintype "passive"))
      (node (ref "T1") (pin "2") (pinfunction "E_2") (pintype "passive"))
      (node (ref "T10") (pin "2") (pinfunction "E_2") (pintype "passive"))
      (node (ref "T2") (pin "2") (pinfunction "E_2") (pintype "passive"))
      (node (ref "T3") (pin "2") (pinfunction "E_2") (pintype "passive"))
      (node (ref "T4") (pin "2") (pinfunction "E_2") (pintype "passive"))
      (node (ref "U1") (pin "15") (pinfunction "IN+_15") (pintype "bidirectional"))
      (node (ref "U1") (pin "16") (pinfunction "IN-_16") (pintype "bidirectional"))
      (node (ref "U1") (pin "3") (pinfunction "GND_3") (pintype "bidirectional"))
      (node (ref "U1") (pin "6") (pinfunction "VEE_6") (pintype "bidirectional"))
      (node (ref "U1") (pin "7") (pinfunction "IN+_7") (pintype "bidirectional"))
      (node (ref "U1") (pin "8") (pinfunction "IN-_8") (pintype "bidirectional"))
      (node (ref "U2") (pin "3") (pinfunction "A_3") (pintype "input"))
      (node (ref "U2") (pin "4") (pinfunction "B_4") (pintype "input"))
      (node (ref "U2") (pin "5") (pinfunction "C_5") (pintype "input"))
      (node (ref "U2") (pin "6") (pinfunction "D_6") (pintype "input"))
      (node (ref "U2") (pin "8") (pinfunction "GND_8") (pintype "power_in"))
      (node (ref "U3") (pin "4") (pinfunction "GND_4") (pintype "passive"))
      (node (ref "U3") (pin "7") (pinfunction "~{G}_7") (pintype "input"))
      (node (ref "U4") (pin "4") (pinfunction "GND_4") (pintype "bidirectional"))
      (node (ref "U6") (pin "3") (pinfunction "IN+_3") (pintype "input"))
      (node (ref "U6") (pin "4") (pinfunction "VEE_4") (pintype "bidirectional"))
      (node (ref "UART") (pin "2") (pinfunction "2_2") (pintype "passive"))
    )
    (net (code "46") (name "HF") (class "Default")
      (node (ref "PCB1") (pin "OUT") (pinfunction "OUT_OUT") (pintype "bidirectional"))
      (node (ref "U3") (pin "2") (pinfunction "B_2") (pintype "input"))
    )
    (net (code "47") (name "HFSEL1") (class "Default")
      (node (ref "IC6") (pin "6") (pinfunction "QG_6") (pintype "tri_state"))
      (node (ref "PCB1") (pin "DIVSEL1") (pinfunction "DIVSEL1_DIVSEL1") (pintype "bidirectional"))
    )
    (net (code "48") (name "HFSEL2") (class "Default")
      (node (ref "IC6") (pin "5") (pinfunction "QF_5") (pintype "tri_state"))
      (node (ref "PCB1") (pin "DIVSEL2") (pinfunction "DIVSEL2_DIVSEL2") (pintype "bidirectional"))
    )
    (net (code "49") (name "INPUTSEL") (class "Default")
      (node (ref "IC6") (pin "1") (pinfunction "QB_1") (pintype "tri_state"))
      (node (ref "U3") (pin "6") (pinfunction "~{A/B}_6") (pintype "input"))
    )
    (net (code "50") (name "I_10A") (class "Default")
      (node (ref "J3") (pin "1@1") (pinfunction "1_1@1") (pintype "bidirectional"))
      (node (ref "J3") (pin "1@2") (pinfunction "2_1@2") (pintype "bidirectional"))
      (node (ref "R16") (pin "2") (pinfunction "2_2") (pintype "passive"))
      (node (ref "R24") (pin "2") (pinfunction "2_2") (pintype "passive"))
    )
    (net (code "51") (name "I_U{slash}I{slash}R") (class "Default")
      (node (ref "F2") (pin "2A") (pinfunction "2A_2A") (pintype "passive"))
      (node (ref "F2") (pin "2B") (pinfunction "2B_2B") (pintype "passive"))
      (node (ref "J2") (pin "1@1") (pinfunction "1_1@1") (pintype "bidirectional"))
      (node (ref "J2") (pin "1@2") (pinfunction "2_1@2") (pintype "bidirectional"))
    )
    (net (code "52") (name "LF") (class "Default")
      (node (ref "IC3") (pin "12") (pinfunction "D_12") (pintype "input"))
      (node (ref "IC3") (pin "8") (pinfunction "~{Q}_8") (pintype "output"))
      (node (ref "SJ1") (pin "1") (pinfunction "1_1") (pintype "passive"))
      (node (ref "U3") (pin "1") (pinfunction "A_1") (pintype "input"))
    )
    (net (code "53") (name "LF_DIRECT") (class "Default")
      (node (ref "IC4") (pin "14") (pinfunction "D5_14") (pintype "input"))
      (node (ref "R12") (pin "1") (pinfunction "1_1") (pintype "passive"))
    )
    (net (code "54") (name "Net-(C1-Pad1)") (class "Default")
      (node (ref "C1") (pin "1") (pinfunction "1_1") (pintype "passive"))
      (node (ref "IN_LF") (pin "1") (pinfunction "1_1") (pintype "passive"))
    )
    (net (code "55") (name "Net-(C1-Pad2)") (class "Default")
      (node (ref "C1") (pin "2") (pinfunction "2_2") (pintype "passive"))
      (node (ref "R1") (pin "1") (pinfunction "1_1") (pintype "passive"))
      (node (ref "R2") (pin "2") (pinfunction "2_2") (pintype "passive"))
      (node (ref "R3") (pin "2") (pinfunction "2_2") (pintype "passive"))
    )
    (net (code "56") (name "Net-(C3-Pad1)") (class "Default")
      (node (ref "C3") (pin "1") (pinfunction "1_1") (pintype "passive"))
      (node (ref "REF10MHZ") (pin "1") (pinfunction "1_1") (pintype "passive"))
    )
    (net (code "57") (name "Net-(C3-Pad2)") (class "Default")
      (node (ref "C3") (pin "2") (pinfunction "2_2") (pintype "passive"))
      (node (ref "R5") (pin "1") (pinfunction "1_1") (pintype "passive"))
      (node (ref "R6") (pin "2") (pinfunction "2_2") (pintype "passive"))
      (node (ref "R7") (pin "2") (pinfunction "2_2") (pintype "passive"))
    )
    (net (code "58") (name "Net-(C5-Pad2)") (class "Default")
      (node (ref "C5") (pin "2") (pinfunction "2_2") (pintype "passive"))
      (node (ref "D1") (pin "A") (pinfunction "A_A") (pintype "passive"))
      (node (ref "D2") (pin "C") (pinfunction "C_C") (pintype "passive"))
      (node (ref "R10") (pin "1") (pinfunction "1_1") (pintype "passive"))
      (node (ref "R11") (pin "2") (pinfunction "2_2") (pintype "passive"))
      (node (ref "R9") (pin "1") (pinfunction "1_1") (pintype "passive"))
    )
    (net (code "59") (name "Net-(D3-PadC)") (class "Default")
      (node (ref "D3") (pin "C") (pinfunction "C_C") (pintype "passive"))
      (node (ref "D4") (pin "A") (pinfunction "A_A") (pintype "passive"))
    )
    (net (code "60") (name "Net-(IC1A-I)") (class "Default")
      (node (ref "IC1") (pin "13") (pinfunction "I_13") (pintype "input"))
      (node (ref "R11") (pin "1") (pinfunction "1_1") (pintype "passive"))
    )
    (net (code "61") (name "Net-(IC3A-CLK)") (class "Default")
      (node (ref "IC3") (pin "3") (pinfunction "CLK_3") (pintype "input"))
      (node (ref "R12") (pin "2") (pinfunction "2_2") (pintype "passive"))
      (node (ref "U1") (pin "4") (pinfunction "OUT_4") (pintype "bidirectional"))
    )
    (net (code "62") (name "Net-(IC3A-D)") (class "Default")
      (node (ref "IC3") (pin "11") (pinfunction "CLK_11") (pintype "input"))
      (node (ref "IC3") (pin "2") (pinfunction "D_2") (pintype "input"))
      (node (ref "IC3") (pin "6") (pinfunction "~{Q}_6") (pintype "output"))
    )
    (net (code "63") (name "Net-(IC4A-D0)") (class "Default")
      (node (ref "IC4") (pin "4") (pinfunction "D0_4") (pintype "input"))
      (node (ref "U2") (pin "11") (pinfunction "QD_11") (pintype "output"))
    )
    (net (code "64") (name "Net-(IC4A-D1)") (class "Default")
      (node (ref "IC4") (pin "3") (pinfunction "D1_3") (pintype "input"))
      (node (ref "U2") (pin "12") (pinfunction "QC_12") (pintype "output"))
    )
    (net (code "65") (name "Net-(IC4A-D2)") (class "Default")
      (node (ref "IC4") (pin "2") (pinfunction "D2_2") (pintype "input"))
      (node (ref "U2") (pin "13") (pinfunction "QB_13") (pintype "output"))
    )
    (net (code "66") (name "Net-(IC4A-D3)") (class "Default")
      (node (ref "IC4") (pin "1") (pinfunction "D3_1") (pintype "input"))
      (node (ref "U2") (pin "14") (pinfunction "QA_14") (pintype "output"))
    )
    (net (code "67") (name "Net-(IC4A-D4)") (class "Default")
      (node (ref "IC4") (pin "15") (pinfunction "D4_15") (pintype "input"))
      (node (ref "R13") (pin "2") (pinfunction "2_2") (pintype "passive"))
    )
    (net (code "68") (name "Net-(IC5A-B)") (class "Default")
      (node (ref "IC5") (pin "4") (pinfunction "B_4") (pintype "input"))
      (node (ref "U1") (pin "12") (pinfunction "OUT_12") (pintype "bidirectional"))
    )
    (net (code "69") (name "Net-(IC6A-QH*)") (class "Default")
      (node (ref "IC6") (pin "9") (pinfunction "QH*_9") (pintype "tri_state"))
      (node (ref "IC7") (pin "14") (pinfunction "SER_14") (pintype "input"))
    )
    (net (code "70") (name "Net-(J4-1)") (class "Default")
      (node (ref "J4") (pin "1@1") (pinfunction "1_1@1") (pintype "bidirectional"))
      (node (ref "R9") (pin "2") (pinfunction "2_2") (pintype "passive"))
    )
    (net (code "71") (name "Net-(K1A--)") (class "Default")
      (node (ref "D11") (pin "A") (pinfunction "A_A") (pintype "passive"))
      (node (ref "D5") (pin "A") (pinfunction "A_A") (pintype "passive"))
      (node (ref "K1") (pin "8") (pinfunction "-_8") (pintype "passive"))
      (node (ref "K4") (pin "8") (pinfunction "-_8") (pintype "passive"))
      (node (ref "T3") (pin "3") (pinfunction "C_3") (pintype "passive"))
    )
    (net (code "72") (name "Net-(K1B-O)") (class "Default")
      (node (ref "K1") (pin "2") (pinfunction "O_2") (pintype "passive"))
      (node (ref "R26") (pin "1") (pinfunction "1_1") (pintype "passive"))
      (node (ref "R27") (pin "2") (pinfunction "2_2") (pintype "passive"))
    )
    (net (code "73") (name "Net-(K1B-P)") (class "Default")
      (node (ref "K1") (pin "3") (pinfunction "P_3") (pintype "passive"))
      (node (ref "K2") (pin "4") (pinfunction "S_4") (pintype "passive"))
    )
    (net (code "74") (name "Net-(K1C-O)") (class "Default")
      (node (ref "K1") (pin "7") (pinfunction "O_7") (pintype "passive"))
      (node (ref "R24") (pin "1") (pinfunction "1_1") (pintype "passive"))
      (node (ref "R25") (pin "2") (pinfunction "2_2") (pintype "passive"))
    )
    (net (code "75") (name "Net-(K1C-P)") (class "Default")
      (node (ref "K1") (pin "6") (pinfunction "P_6") (pintype "passive"))
      (node (ref "K2") (pin "2") (pinfunction "O_2") (pintype "passive"))
    )
    (net (code "76") (name "Net-(K1C-S)") (class "Default")
      (node (ref "K1") (pin "5") (pinfunction "S_5") (pintype "passive"))
      (node (ref "R25") (pin "1") (pinfunction "1_1") (pintype "passive"))
      (node (ref "R26") (pin "2") (pinfunction "2_2") (pintype "passive"))
    )
    (net (code "77") (name "Net-(K2A--)") (class "Default")
      (node (ref "D6") (pin "A") (pinfunction "A_A") (pintype "passive"))
      (node (ref "K2") (pin "8") (pinfunction "-_8") (pintype "passive"))
      (node (ref "T2") (pin "3") (pinfunction "C_3") (pintype "passive"))
    )
    (net (code "78") (name "Net-(K2C-O)") (class "Default")
      (node (ref "K2") (pin "7") (pinfunction "O_7") (pintype "passive"))
      (node (ref "K4") (pin "6") (pinfunction "P_6") (pintype "passive"))
    )
    (net (code "79") (name "Net-(K2C-S)") (class "Default")
      (node (ref "K2") (pin "5") (pinfunction "S_5") (pintype "passive"))
      (node (ref "K4") (pin "3") (pinfunction "P_3") (pintype "passive"))
    )
    (net (code "80") (name "Net-(K3A--)") (class "Default")
      (node (ref "D7") (pin "A") (pinfunction "A_A") (pintype "passive"))
      (node (ref "K3") (pin "8") (pinfunction "-_8") (pintype "passive"))
      (node (ref "T4") (pin "3") (pinfunction "C_3") (pintype "passive"))
    )
    (net (code "81") (name "Net-(K3B-P)") (class "Default")
      (node (ref "K3") (pin "3") (pinfunction "P_3") (pintype "passive"))
      (node (ref "K5") (pin "7") (pinfunction "O_7") (pintype "passive"))
    )
    (net (code "82") (name "Net-(K4B-O)") (class "Default")
      (node (ref "K4") (pin "2") (pinfunction "O_2") (pintype "passive"))
      (node (ref "R30") (pin "1") (pinfunction "1_1") (pintype "passive"))
      (node (ref "R31") (pin "2") (pinfunction "2_2") (pintype "passive"))
    )
    (net (code "83") (name "Net-(K4B-S)") (class "Default")
      (node (ref "K4") (pin "4") (pinfunction "S_4") (pintype "passive"))
      (node (ref "R31") (pin "1") (pinfunction "1_1") (pintype "passive"))
      (node (ref "R32") (pin "2") (pinfunction "2_2") (pintype "passive"))
    )
    (net (code "84") (name "Net-(K4C-O)") (class "Default")
      (node (ref "K4") (pin "7") (pinfunction "O_7") (pintype "passive"))
      (node (ref "R28") (pin "1") (pinfunction "1_1") (pintype "passive"))
      (node (ref "R29") (pin "2") (pinfunction "2_2") (pintype "passive"))
    )
    (net (code "85") (name "Net-(K4C-S)") (class "Default")
      (node (ref "K4") (pin "5") (pinfunction "S_5") (pintype "passive"))
      (node (ref "R29") (pin "1") (pinfunction "1_1") (pintype "passive"))
      (node (ref "R30") (pin "2") (pinfunction "2_2") (pintype "passive"))
    )
    (net (code "86") (name "Net-(K5A--)") (class "Default")
      (node (ref "D10") (pin "A") (pinfunction "A_A") (pintype "passive"))
      (node (ref "K5") (pin "8") (pinfunction "-_8") (pintype "passive"))
      (node (ref "T10") (pin "3") (pinfunction "C_3") (pintype "passive"))
    )
    (net (code "87") (name "Net-(K5B-S)") (class "Default")
      (node (ref "K5") (pin "4") (pinfunction "S_4") (pintype "passive"))
      (node (ref "K5") (pin "5") (pinfunction "S_5") (pintype "passive"))
      (node (ref "R37") (pin "1") (pinfunction "1_1") (pintype "passive"))
      (node (ref "R40") (pin "1") (pinfunction "1_1") (pintype "passive"))
      (node (ref "R43") (pin "1") (pinfunction "1_1") (pintype "passive"))
      (node (ref "R46") (pin "1") (pinfunction "1_1") (pintype "passive"))
      (node (ref "R49") (pin "1") (pinfunction "1_1") (pintype "passive"))
    )
    (net (code "88") (name "Net-(K5C-P)") (class "Default")
      (node (ref "F2") (pin "1A") (pinfunction "1A_1A") (pintype "passive"))
      (node (ref "F2") (pin "1B") (pinfunction "1B_1B") (pintype "passive"))
      (node (ref "K5") (pin "6") (pinfunction "P_6") (pintype "passive"))
    )
    (net (code "89") (name "Net-(R4-S)") (class "Default")
      (node (ref "C2") (pin "2") (pinfunction "2_2") (pintype "passive"))
      (node (ref "R4") (pin "2") (pinfunction "S_2") (pintype "passive"))
      (node (ref "U1") (pin "1") (pinfunction "IN-_1") (pintype "bidirectional"))
    )
    (net (code "90") (name "Net-(R8-S)") (class "Default")
      (node (ref "C4") (pin "2") (pinfunction "2_2") (pintype "passive"))
      (node (ref "R8") (pin "2") (pinfunction "S_2") (pintype "passive"))
      (node (ref "U1") (pin "9") (pinfunction "IN-_9") (pintype "bidirectional"))
    )
    (net (code "91") (name "Net-(R36-Pad2)") (class "Default")
      (node (ref "R36") (pin "2") (pinfunction "2_2") (pintype "passive"))
      (node (ref "R38") (pin "1") (pinfunction "1_1") (pintype "passive"))
      (node (ref "T5") (pin "B") (pinfunction "B_B") (pintype "passive"))
    )
    (net (code "92") (name "Net-(R37-Pad2)") (class "Default")
      (node (ref "R37") (pin "2") (pinfunction "2_2") (pintype "passive"))
      (node (ref "T5") (pin "C") (pinfunction "C_C") (pintype "passive"))
    )
    (net (code "93") (name "Net-(R39-Pad2)") (class "Default")
      (node (ref "R39") (pin "2") (pinfunction "2_2") (pintype "passive"))
      (node (ref "R41") (pin "1") (pinfunction "1_1") (pintype "passive"))
      (node (ref "T6") (pin "B") (pinfunction "B_B") (pintype "passive"))
    )
    (net (code "94") (name "Net-(R40-Pad2)") (class "Default")
      (node (ref "R40") (pin "2") (pinfunction "2_2") (pintype "passive"))
      (node (ref "T6") (pin "C") (pinfunction "C_C") (pintype "passive"))
    )
    (net (code "95") (name "Net-(R42-Pad2)") (class "Default")
      (node (ref "R42") (pin "2") (pinfunction "2_2") (pintype "passive"))
      (node (ref "R44") (pin "1") (pinfunction "1_1") (pintype "passive"))
      (node (ref "T7") (pin "B") (pinfunction "B_B") (pintype "passive"))
    )
    (net (code "96") (name "Net-(R43-Pad2)") (class "Default")
      (node (ref "R43") (pin "2") (pinfunction "2_2") (pintype "passive"))
      (node (ref "T7") (pin "C") (pinfunction "C_C") (pintype "passive"))
    )
    (net (code "97") (name "Net-(R45-Pad2)") (class "Default")
      (node (ref "R45") (pin "2") (pinfunction "2_2") (pintype "passive"))
      (node (ref "R47") (pin "1") (pinfunction "1_1") (pintype "passive"))
      (node (ref "T8") (pin "B") (pinfunction "B_B") (pintype "passive"))
    )
    (net (code "98") (name "Net-(R46-Pad2)") (class "Default")
      (node (ref "R46") (pin "2") (pinfunction "2_2") (pintype "passive"))
      (node (ref "T8") (pin "C") (pinfunction "C_C") (pintype "passive"))
    )
    (net (code "99") (name "Net-(R48-Pad2)") (class "Default")
      (node (ref "R48") (pin "2") (pinfunction "2_2") (pintype "passive"))
      (node (ref "R50") (pin "1") (pinfunction "1_1") (pintype "passive"))
      (node (ref "T9") (pin "B") (pinfunction "B_B") (pintype "passive"))
    )
    (net (code "100") (name "Net-(R49-Pad2)") (class "Default")
      (node (ref "R49") (pin "2") (pinfunction "2_2") (pintype "passive"))
      (node (ref "T9") (pin "C") (pinfunction "C_C") (pintype "passive"))
    )
    (net (code "101") (name "Net-(T1-B)") (class "Default")
      (node (ref "R22") (pin "2") (pinfunction "2_2") (pintype "passive"))
      (node (ref "T1") (pin "1") (pinfunction "B_1") (pintype "passive"))
    )
    (net (code "102") (name "Net-(T2-B)") (class "Default")
      (node (ref "R33") (pin "2") (pinfunction "2_2") (pintype "passive"))
      (node (ref "T2") (pin "1") (pinfunction "B_1") (pintype "passive"))
    )
    (net (code "103") (name "Net-(T3-B)") (class "Default")
      (node (ref "R34") (pin "2") (pinfunction "2_2") (pintype "passive"))
      (node (ref "T3") (pin "1") (pinfunction "B_1") (pintype "passive"))
    )
    (net (code "104") (name "Net-(T4-B)") (class "Default")
      (node (ref "R35") (pin "2") (pinfunction "2_2") (pintype "passive"))
      (node (ref "T4") (pin "1") (pinfunction "B_1") (pintype "passive"))
    )
    (net (code "105") (name "Net-(T10-B)") (class "Default")
      (node (ref "R52") (pin "2") (pinfunction "2_2") (pintype "passive"))
      (node (ref "T10") (pin "1") (pinfunction "B_1") (pintype "passive"))
    )
    (net (code "106") (name "Net-(U1A-IN+)") (class "Default")
      (node (ref "R3") (pin "1") (pinfunction "1_1") (pintype "passive"))
      (node (ref "U1") (pin "2") (pinfunction "IN+_2") (pintype "bidirectional"))
    )
    (net (code "107") (name "Net-(U1C-IN+)") (class "Default")
      (node (ref "R7") (pin "1") (pinfunction "1_1") (pintype "passive"))
      (node (ref "U1") (pin "10") (pinfunction "IN+_10") (pintype "bidirectional"))
    )
    (net (code "108") (name "Net-(U4-C1+)") (class "Default")
      (node (ref "C14") (pin "2") (pinfunction "2_2") (pintype "passive"))
      (node (ref "U4") (pin "5") (pinfunction "C1+_5") (pintype "bidirectional"))
    )
    (net (code "109") (name "Net-(U4-C1-)") (class "Default")
      (node (ref "C14") (pin "1") (pinfunction "1_1") (pintype "passive"))
      (node (ref "U4") (pin "3") (pinfunction "C1-_3") (pintype "bidirectional"))
    )
    (net (code "110") (name "Net-(U5A-IN-)") (class "Default")
      (node (ref "R17") (pin "2") (pinfunction "2_2") (pintype "passive"))
      (node (ref "R51") (pin "2") (pinfunction "2_2") (pintype "passive"))
      (node (ref "U5") (pin "2") (pinfunction "IN-_2") (pintype "input"))
      (node (ref "U5") (pin "6") (pinfunction "OUT_6") (pintype "output"))
    )
    (net (code "111") (name "Net-(U6A-IN-)") (class "Default")
      (node (ref "R17") (pin "1") (pinfunction "1_1") (pintype "passive"))
      (node (ref "R18") (pin "2") (pinfunction "2_2") (pintype "passive"))
      (node (ref "U6") (pin "2") (pinfunction "IN-_2") (pintype "input"))
    )
    (net (code "112") (name "Net-(U6A-OUT)") (class "Default")
      (node (ref "D3") (pin "A") (pinfunction "A_A") (pintype "passive"))
      (node (ref "R22") (pin "1") (pinfunction "1_1") (pintype "passive"))
      (node (ref "U6") (pin "1") (pinfunction "OUT_1") (pintype "output"))
    )
    (net (code "113") (name "Net-(U6B-IN+)") (class "Default")
      (node (ref "D4") (pin "C") (pinfunction "C_C") (pintype "passive"))
      (node (ref "R18") (pin "1") (pinfunction "1_1") (pintype "passive"))
      (node (ref "U6") (pin "5") (pinfunction "IN+_5") (pintype "input"))
    )
    (net (code "114") (name "Net-(U6B-IN-)") (class "Default")
      (node (ref "R19") (pin "2") (pinfunction "2_2") (pintype "passive"))
      (node (ref "R20") (pin "1") (pinfunction "1_1") (pintype "passive"))
      (node (ref "U6") (pin "6") (pinfunction "IN-_6") (pintype "input"))
    )
    (net (code "115") (name "PA0") (class "Default")
      (node (ref "C16") (pin "+") (pinfunction "+_+") (pintype "passive"))
      (node (ref "DMM_RIGHT") (pin "2") (pinfunction "2_2") (pintype "passive"))
      (node (ref "R21") (pin "2") (pinfunction "2_2") (pintype "passive"))
    )
    (net (code "116") (name "PA1") (class "Default")
      (node (ref "C23") (pin "+") (pinfunction "+_+") (pintype "passive"))
      (node (ref "D8") (pin "C") (pinfunction "C_C") (pintype "passive"))
      (node (ref "D9") (pin "A") (pinfunction "A_A") (pintype "passive"))
      (node (ref "DMM_RIGHT") (pin "4") (pinfunction "4_4") (pintype "passive"))
      (node (ref "R51") (pin "1") (pinfunction "1_1") (pintype "passive"))
    )
    (net (code "117") (name "PA2") (class "Default")
      (node (ref "DMM_RIGHT") (pin "6") (pinfunction "6_6") (pintype "passive"))
      (node (ref "IC6") (pin "14") (pinfunction "SER_14") (pintype "input"))
    )
    (net (code "118") (name "PB0") (class "Default")
      (node (ref "DMM_LEFT") (pin "1") (pinfunction "1_1") (pintype "passive"))
      (node (ref "R53") (pin "1") (pinfunction "1_1") (pintype "passive"))
    )
    (net (code "119") (name "PB1") (class "Default")
      (node (ref "DMM_LEFT") (pin "3") (pinfunction "3_3") (pintype "passive"))
      (node (ref "R60") (pin "1") (pinfunction "1_1") (pintype "passive"))
    )
    (net (code "120") (name "PB2") (class "Default")
      (node (ref "DMM_LEFT") (pin "5") (pinfunction "5_5") (pintype "passive"))
      (node (ref "R23") (pin "2") (pinfunction "2_2") (pintype "passive"))
      (node (ref "T1") (pin "3") (pinfunction "C_3") (pintype "passive"))
    )
    (net (code "121") (name "PD2") (class "Default")
      (node (ref "DMM_LEFT") (pin "31") (pinfunction "31_31") (pintype "passive"))
      (node (ref "R55") (pin "2") (pinfunction "2_2") (pintype "passive"))
    )
    (net (code "122") (name "PD3") (class "Default")
      (node (ref "DMM_LEFT") (pin "33") (pinfunction "33_33") (pintype "passive"))
      (node (ref "R57") (pin "2") (pinfunction "2_2") (pintype "passive"))
    )
    (net (code "123") (name "PD4") (class "Default")
      (node (ref "DMM_LEFT") (pin "35") (pinfunction "35_35") (pintype "passive"))
      (node (ref "R56") (pin "2") (pinfunction "2_2") (pintype "passive"))
    )
    (net (code "124") (name "PD5") (class "Default")
      (node (ref "DMM_LEFT") (pin "37") (pinfunction "37_37") (pintype "passive"))
      (node (ref "IC6") (pin "12") (pinfunction "RCK_12") (pintype "input"))
      (node (ref "IC7") (pin "12") (pinfunction "RCK_12") (pintype "input"))
    )
    (net (code "125") (name "PD6") (class "Default")
      (node (ref "DMM_LEFT") (pin "39") (pinfunction "39_39") (pintype "passive"))
      (node (ref "R54") (pin "1") (pinfunction "1_1") (pintype "passive"))
    )
    (net (code "126") (name "PD7") (class "Default")
      (node (ref "DMM_RIGHT") (pin "40") (pinfunction "40_40") (pintype "passive"))
      (node (ref "IC6") (pin "11") (pinfunction "SCK_11") (pintype "input"))
      (node (ref "IC7") (pin "11") (pinfunction "SCK_11") (pintype "input"))
    )
    (net (code "127") (name "RANGE_LSB") (class "Default")
      (node (ref "IC6") (pin "7") (pinfunction "QH_7") (pintype "tri_state"))
      (node (ref "R34") (pin "1") (pinfunction "1_1") (pintype "passive"))
    )
    (net (code "128") (name "RANGE_MSB") (class "Default")
      (node (ref "IC7") (pin "15") (pinfunction "QA_15") (pintype "tri_state"))
      (node (ref "R33") (pin "1") (pinfunction "1_1") (pintype "passive"))
    )
    (net (code "129") (name "R_RANGE1") (class "Default")
      (node (ref "IC7") (pin "5") (pinfunction "QF_5") (pintype "tri_state"))
      (node (ref "R36") (pin "1") (pinfunction "1_1") (pintype "passive"))
    )
    (net (code "130") (name "R_RANGE2") (class "Default")
      (node (ref "IC7") (pin "4") (pinfunction "QE_4") (pintype "tri_state"))
      (node (ref "R39") (pin "1") (pinfunction "1_1") (pintype "passive"))
    )
    (net (code "131") (name "R_RANGE3") (class "Default")
      (node (ref "IC7") (pin "3") (pinfunction "QD_3") (pintype "tri_state"))
      (node (ref "R42") (pin "1") (pinfunction "1_1") (pintype "passive"))
    )
    (net (code "132") (name "R_RANGE4") (class "Default")
      (node (ref "IC7") (pin "2") (pinfunction "QC_2") (pintype "tri_state"))
      (node (ref "R45") (pin "1") (pinfunction "1_1") (pintype "passive"))
    )
    (net (code "133") (name "R_RANGE5") (class "Default")
      (node (ref "IC7") (pin "1") (pinfunction "QB_1") (pintype "tri_state"))
      (node (ref "R48") (pin "1") (pinfunction "1_1") (pintype "passive"))
    )
    (net (code "134") (name "R_SELECTOR") (class "Default")
      (node (ref "IC7") (pin "7") (pinfunction "QH_7") (pintype "tri_state"))
      (node (ref "R52") (pin "1") (pinfunction "1_1") (pintype "passive"))
    )
    (net (code "135") (name "TTL") (class "Default")
      (node (ref "IC1") (pin "12") (pinfunction "O_12") (pintype "output"))
      (node (ref "IC4") (pin "13") (pinfunction "D6_13") (pintype "input"))
    )
    (net (code "136") (name "U_I_SELECTOR") (class "Default")
      (node (ref "IC7") (pin "6") (pinfunction "QG_6") (pintype "tri_state"))
      (node (ref "R35") (pin "1") (pinfunction "1_1") (pintype "passive"))
    )
    (net (code "137") (name "VCC") (class "Default")
      (node (ref "C10") (pin "1") (pinfunction "1_1") (pintype "passive"))
      (node (ref "C11") (pin "1") (pinfunction "1_1") (pintype "passive"))
      (node (ref "C12") (pin "1") (pinfunction "1_1") (pintype "passive"))
      (node (ref "C13") (pin "1") (pinfunction "1_1") (pintype "passive"))
      (node (ref "C17") (pin "1") (pinfunction "1_1") (pintype "passive"))
      (node (ref "C18") (pin "1") (pinfunction "1_1") (pintype "passive"))
      (node (ref "C20") (pin "+") (pinfunction "+_+") (pintype "passive"))
      (node (ref "C21") (pin "1") (pinfunction "1_1") (pintype "passive"))
      (node (ref "C22") (pin "1") (pinfunction "1_1") (pintype "passive"))
      (node (ref "C6") (pin "2") (pinfunction "2_2") (pintype "passive"))
      (node (ref "C7") (pin "1") (pinfunction "1_1") (pintype "passive"))
      (node (ref "C8") (pin "1") (pinfunction "1_1") (pintype "passive"))
      (node (ref "C9") (pin "1") (pinfunction "1_1") (pintype "passive"))
      (node (ref "D1") (pin "C") (pinfunction "C_C") (pintype "passive"))
      (node (ref "D10") (pin "C") (pinfunction "C_C") (pintype "passive"))
      (node (ref "D11") (pin "C") (pinfunction "C_C") (pintype "passive"))
      (node (ref "D5") (pin "C") (pinfunction "C_C") (pintype "passive"))
      (node (ref "D6") (pin "C") (pinfunction "C_C") (pintype "passive"))
      (node (ref "D7") (pin "C") (pinfunction "C_C") (pintype "passive"))
      (node (ref "D9") (pin "C") (pinfunction "C_C") (pintype "passive"))
      (node (ref "DMM_LEFT") (pin "19") (pinfunction "19_19") (pintype "passive"))
      (node (ref "DMM_LEFT") (pin "20") (pinfunction "20_20") (pintype "passive"))
      (node (ref "IC1") (pin "14") (pinfunction "VCC_14") (pintype "power_in"))
      (node (ref "IC2") (pin "3") (pinfunction "VIN_3") (pintype "input"))
      (node (ref "IC3") (pin "1") (pinfunction "CLR_1") (pintype "input"))
      (node (ref "IC3") (pin "10") (pinfunction "PRE_10") (pintype "input"))
      (node (ref "IC3") (pin "13") (pinfunction "CLR_13") (pintype "input"))
      (node (ref "IC3") (pin "14") (pinfunction "VCC_14") (pintype "power_in"))
      (node (ref "IC3") (pin "4") (pinfunction "PRE_4") (pintype "input"))
      (node (ref "IC4") (pin "16") (pinfunction "VCC_16") (pintype "power_in"))
      (node (ref "IC5") (pin "16") (pinfunction "VCC_16") (pintype "power_in"))
      (node (ref "IC6") (pin "10") (pinfunction "SCL_10") (pintype "input"))
      (node (ref "IC6") (pin "16") (pinfunction "VCC_16") (pintype "power_in"))
      (node (ref "IC7") (pin "10") (pinfunction "SCL_10") (pintype "input"))
      (node (ref "IC7") (pin "16") (pinfunction "VCC_16") (pintype "power_in"))
      (node (ref "K1") (pin "1") (pinfunction "+_1") (pintype "passive"))
      (node (ref "K2") (pin "1") (pinfunction "+_1") (pintype "passive"))
      (node (ref "K3") (pin "1") (pinfunction "+_1") (pintype "passive"))
      (node (ref "K4") (pin "1") (pinfunction "+_1") (pintype "passive"))
      (node (ref "K5") (pin "1") (pinfunction "+_1") (pintype "passive"))
      (node (ref "PCB1") (pin "VCC") (pinfunction "VCC_VCC") (pintype "bidirectional"))
      (node (ref "R1") (pin "2") (pinfunction "2_2") (pintype "passive"))
      (node (ref "R23") (pin "1") (pinfunction "1_1") (pintype "passive"))
      (node (ref "R4") (pin "1") (pinfunction "E_1") (pintype "passive"))
      (node (ref "R5") (pin "2") (pinfunction "2_2") (pintype "passive"))
      (node (ref "R8") (pin "1") (pinfunction "E_1") (pintype "passive"))
      (node (ref "U1") (pin "11") (pinfunction "VDD_11") (pintype "bidirectional"))
      (node (ref "U1") (pin "14") (pinfunction "VCC_14") (pintype "bidirectional"))
      (node (ref "U2") (pin "10") (pinfunction "ENT_10") (pintype "input"))
      (node (ref "U2") (pin "16") (pinfunction "VCC_16") (pintype "power_in"))
      (node (ref "U2") (pin "9") (pinfunction "~{LOAD}_9") (pintype "input"))
      (node (ref "U3") (pin "8") (pinfunction "VCC_8") (pintype "power_in"))
      (node (ref "U4") (pin "2") (pinfunction "V_IN_2") (pintype "bidirectional"))
      (node (ref "U5") (pin "7") (pinfunction "VCC_7") (pintype "bidirectional"))
      (node (ref "U6") (pin "8") (pinfunction "VCC_8") (pintype "bidirectional"))
    )
    (net (code "138") (name "unconnected-(DMM_LEFT-Pad2)") (class "Default")
      (node (ref "DMM_LEFT") (pin "2") (pinfunction "2_2") (pintype "passive"))
    )
    (net (code "139") (name "unconnected-(DMM_LEFT-Pad4)") (class "Default")
      (node (ref "DMM_LEFT") (pin "4") (pinfunction "4_4") (pintype "passive"))
    )
    (net (code "140") (name "unconnected-(DMM_LEFT-Pad6)") (class "Default")
      (node (ref "DMM_LEFT") (pin "6") (pinfunction "6_6") (pintype "passive"))
    )
    (net (code "141") (name "unconnected-(DMM_LEFT-Pad32)") (class "Default")
      (node (ref "DMM_LEFT") (pin "32") (pinfunction "32_32") (pintype "passive"))
    )
    (net (code "142") (name "unconnected-(DMM_LEFT-Pad34)") (class "Default")
      (node (ref "DMM_LEFT") (pin "34") (pinfunction "34_34") (pintype "passive"))
    )
    (net (code "143") (name "unconnected-(DMM_LEFT-Pad36)") (class "Default")
      (node (ref "DMM_LEFT") (pin "36") (pinfunction "36_36") (pintype "passive"))
    )
    (net (code "144") (name "unconnected-(DMM_LEFT-Pad38)") (class "Default")
      (node (ref "DMM_LEFT") (pin "38") (pinfunction "38_38") (pintype "passive"))
    )
    (net (code "145") (name "unconnected-(DMM_LEFT-Pad40)") (class "Default")
      (node (ref "DMM_LEFT") (pin "40") (pinfunction "40_40") (pintype "passive"))
    )
    (net (code "146") (name "unconnected-(DMM_RIGHT-Pad1)") (class "Default")
      (node (ref "DMM_RIGHT") (pin "1") (pinfunction "1_1") (pintype "passive"))
    )
    (net (code "147") (name "unconnected-(DMM_RIGHT-Pad3)") (class "Default")
      (node (ref "DMM_RIGHT") (pin "3") (pinfunction "3_3") (pintype "passive"))
    )
    (net (code "148") (name "unconnected-(DMM_RIGHT-Pad5)") (class "Default")
      (node (ref "DMM_RIGHT") (pin "5") (pinfunction "5_5") (pintype "passive"))
    )
    (net (code "149") (name "unconnected-(DMM_RIGHT-Pad39)") (class "Default")
      (node (ref "DMM_RIGHT") (pin "39") (pinfunction "39_39") (pintype "passive"))
    )
    (net (code "150") (name "unconnected-(IC1B-O-Pad10)") (class "Default")
      (node (ref "IC1") (pin "10") (pinfunction "O_10") (pintype "output"))
    )
    (net (code "151") (name "unconnected-(IC1C-O-Pad8)") (class "Default")
      (node (ref "IC1") (pin "8") (pinfunction "O_8") (pintype "output"))
    )
    (net (code "152") (name "unconnected-(IC1D-O-Pad2)") (class "Default")
      (node (ref "IC1") (pin "2") (pinfunction "O_2") (pintype "output"))
    )
    (net (code "153") (name "unconnected-(IC1E-O-Pad4)") (class "Default")
      (node (ref "IC1") (pin "4") (pinfunction "O_4") (pintype "output"))
    )
    (net (code "154") (name "unconnected-(IC1F-O-Pad6)") (class "Default")
      (node (ref "IC1") (pin "6") (pinfunction "O_6") (pintype "output"))
    )
    (net (code "155") (name "unconnected-(IC3A-Q-Pad5)") (class "Default")
      (node (ref "IC3") (pin "5") (pinfunction "Q_5") (pintype "output"))
    )
    (net (code "156") (name "unconnected-(IC3B-Q-Pad9)") (class "Default")
      (node (ref "IC3") (pin "9") (pinfunction "Q_9") (pintype "output"))
    )
    (net (code "157") (name "unconnected-(IC4A-W-Pad6)") (class "Default")
      (node (ref "IC4") (pin "6") (pinfunction "W_6") (pintype "output"))
    )
    (net (code "158") (name "unconnected-(IC5A-QA-Pad3)") (class "Default")
      (node (ref "IC5") (pin "3") (pinfunction "QA_3") (pintype "output"))
    )
    (net (code "159") (name "unconnected-(IC5A-QC-Pad6)") (class "Default")
      (node (ref "IC5") (pin "6") (pinfunction "QC_6") (pintype "output"))
    )
    (net (code "160") (name "unconnected-(IC5A-QD-Pad7)") (class "Default")
      (node (ref "IC5") (pin "7") (pinfunction "QD_7") (pintype "output"))
    )
    (net (code "161") (name "unconnected-(IC5B-QA-Pad13)") (class "Default")
      (node (ref "IC5") (pin "13") (pinfunction "QA_13") (pintype "output"))
    )
    (net (code "162") (name "unconnected-(IC5B-QB-Pad11)") (class "Default")
      (node (ref "IC5") (pin "11") (pinfunction "QB_11") (pintype "output"))
    )
    (net (code "163") (name "unconnected-(IC5B-QC-Pad10)") (class "Default")
      (node (ref "IC5") (pin "10") (pinfunction "QC_10") (pintype "output"))
    )
    (net (code "164") (name "unconnected-(IC5B-QD-Pad9)") (class "Default")
      (node (ref "IC5") (pin "9") (pinfunction "QD_9") (pintype "output"))
    )
    (net (code "165") (name "unconnected-(IC7A-QH*-Pad9)") (class "Default")
      (node (ref "IC7") (pin "9") (pinfunction "QH*_9") (pintype "tri_state"))
    )
    (net (code "166") (name "unconnected-(J4-2-Pad1@2)") (class "Default")
      (node (ref "J4") (pin "1@2") (pinfunction "2_1@2") (pintype "bidirectional"))
    )
    (net (code "167") (name "unconnected-(U1B-OUT-Pad5)") (class "Default")
      (node (ref "U1") (pin "5") (pinfunction "OUT_5") (pintype "bidirectional"))
    )
    (net (code "168") (name "unconnected-(U1D-OUT-Pad13)") (class "Default")
      (node (ref "U1") (pin "13") (pinfunction "OUT_13") (pintype "bidirectional"))
    )
    (net (code "169") (name "unconnected-(U2A-RCO-Pad15)") (class "Default")
      (node (ref "U2") (pin "15") (pinfunction "RCO_15") (pintype "output"))
    )
    (net (code "170") (name "unconnected-(U3-~{Y}-Pad3)") (class "Default")
      (node (ref "U3") (pin "3") (pinfunction "~{Y}_3") (pintype "output"))
    )
  )
)
